# AMR3350.net
KiCad netlist of a schematic drawn in EAGLE
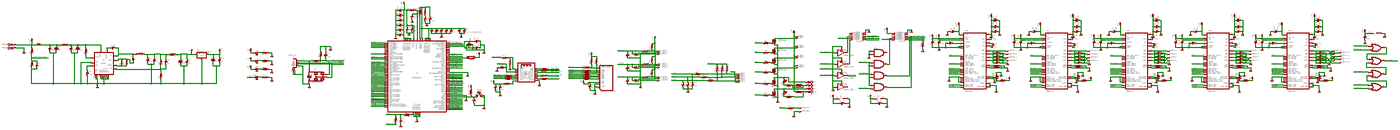
[diagram p0: schematic, sheet 1, overview]
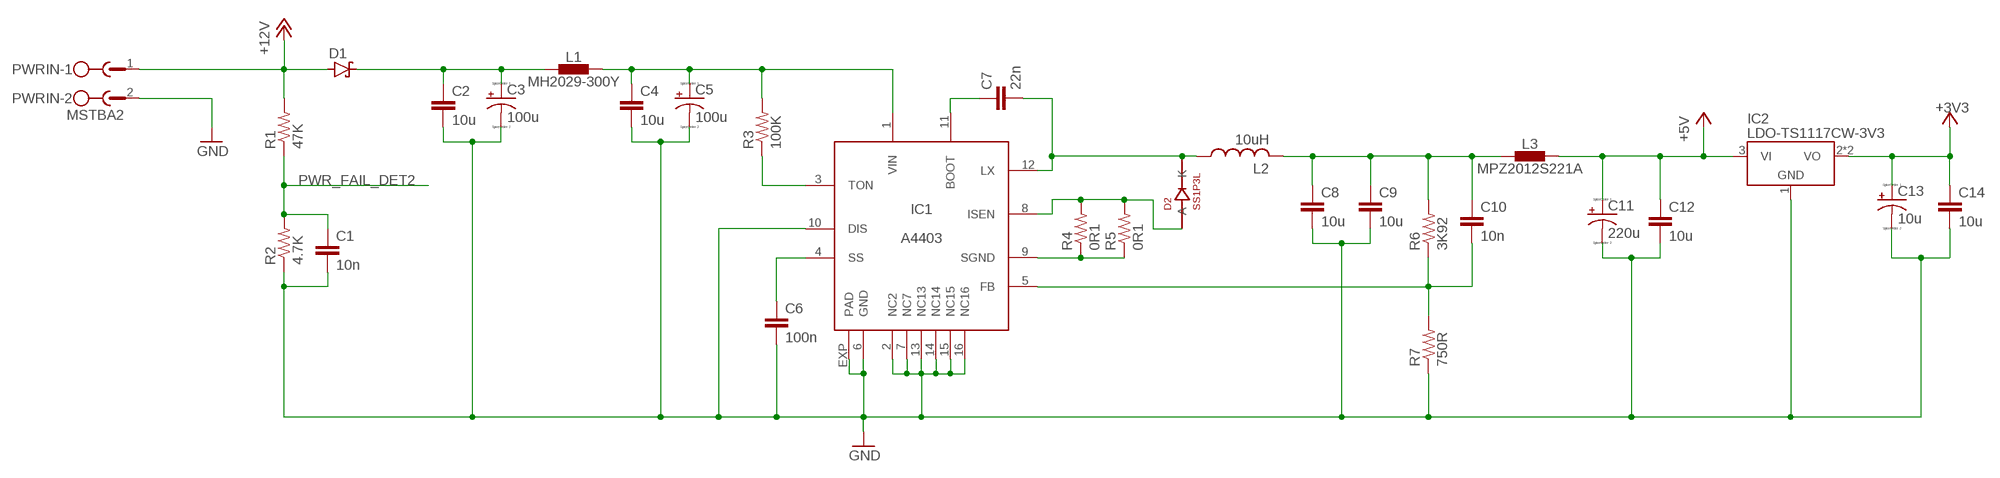
[diagram p1: schematic, sheet 1, part 1 of 6]
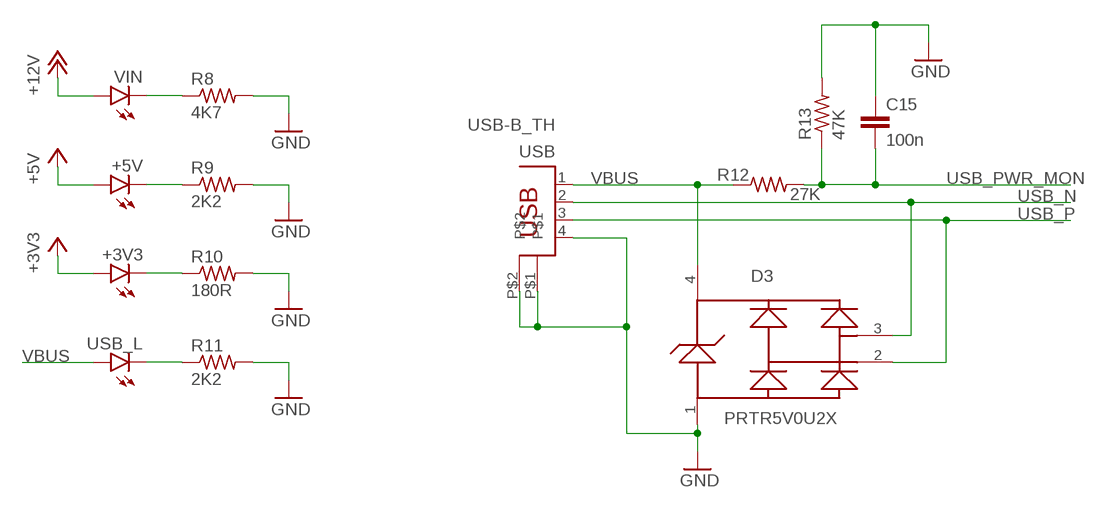
[diagram p2: schematic, sheet 1, part 2 of 6]
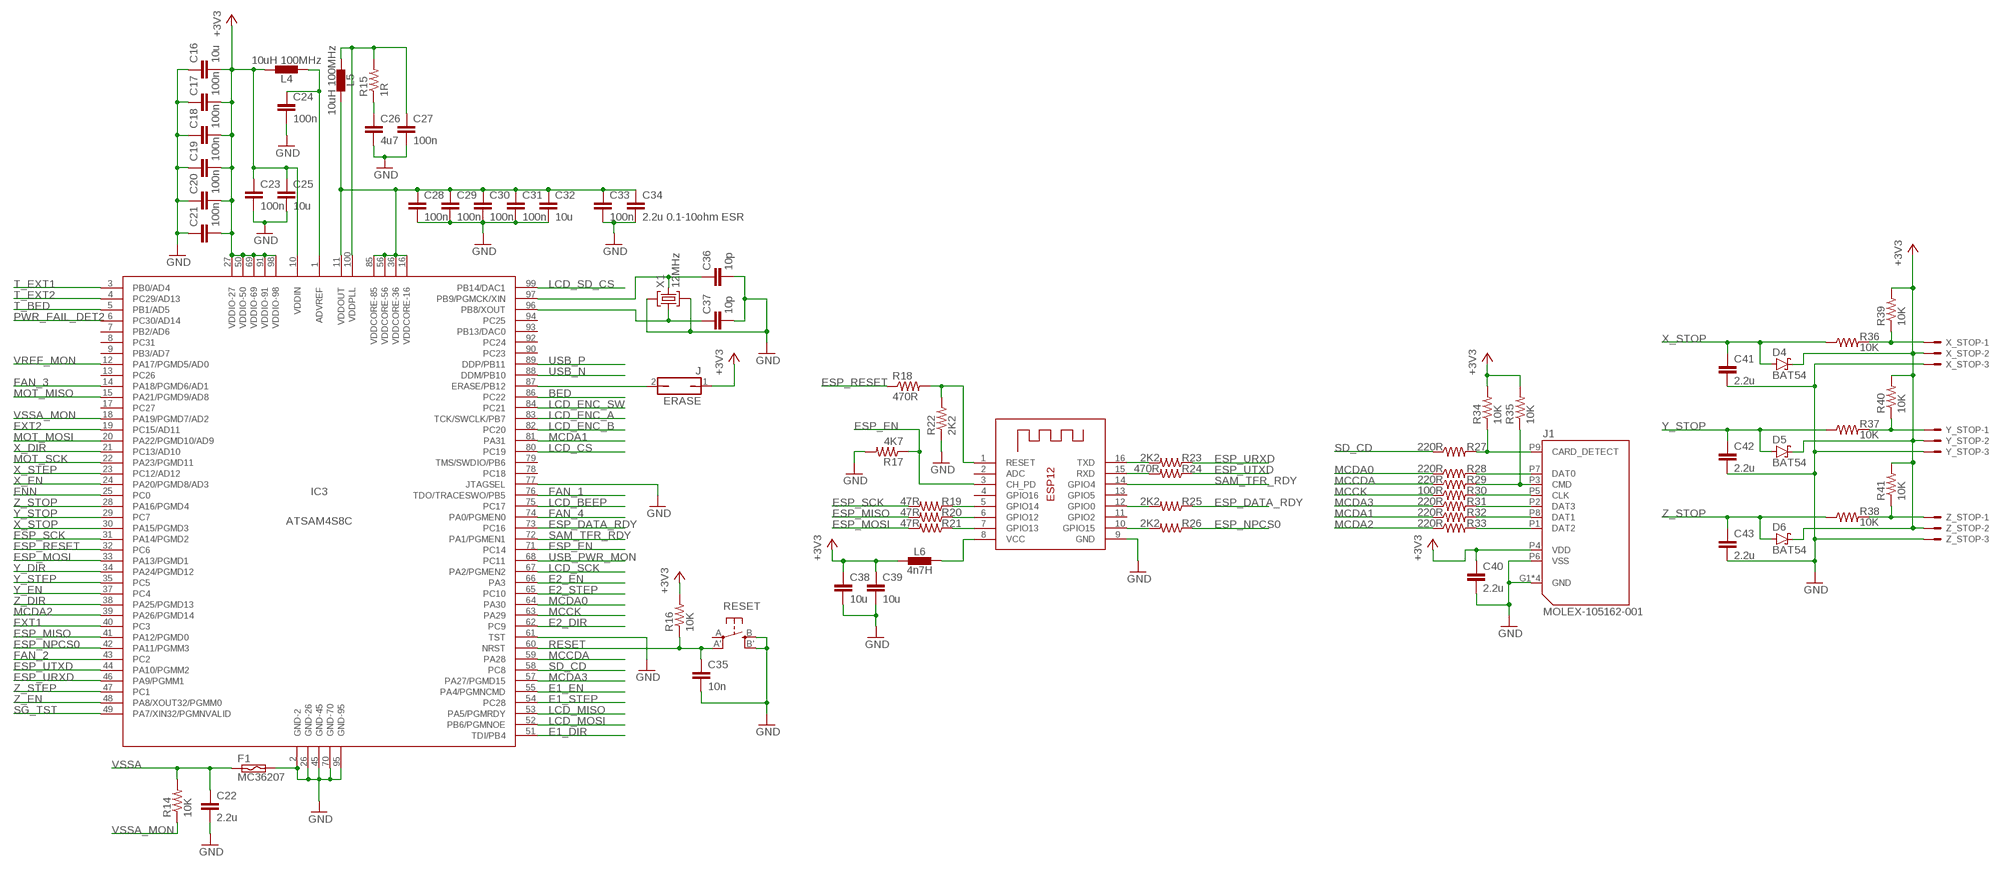
[diagram p3: schematic, sheet 1, part 3 of 6]
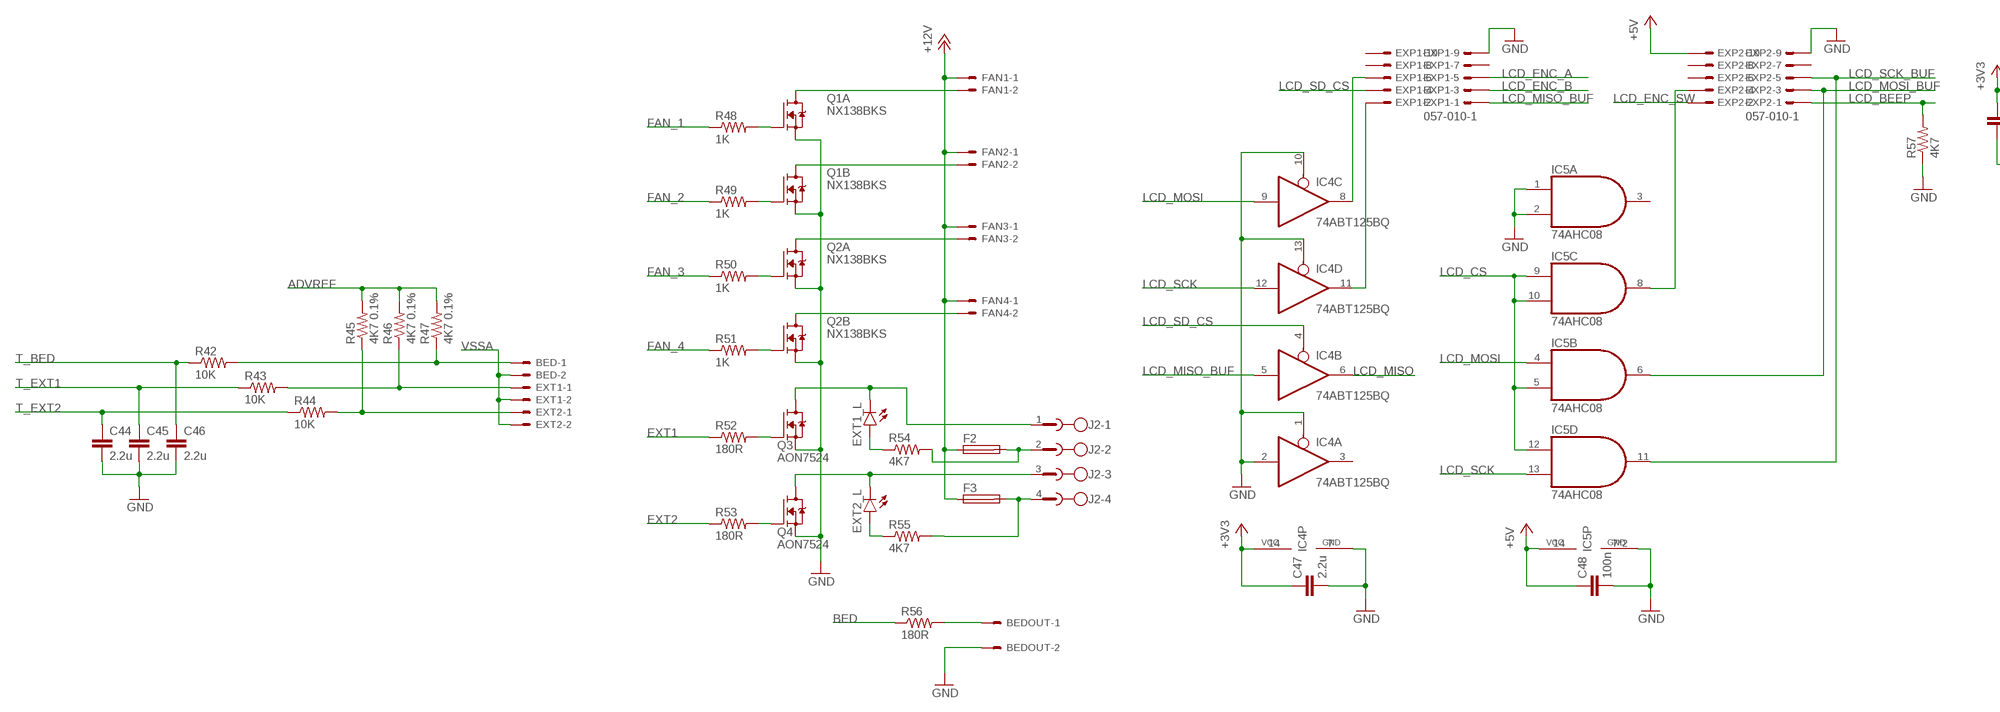
[diagram p4: schematic, sheet 1, part 4 of 6]
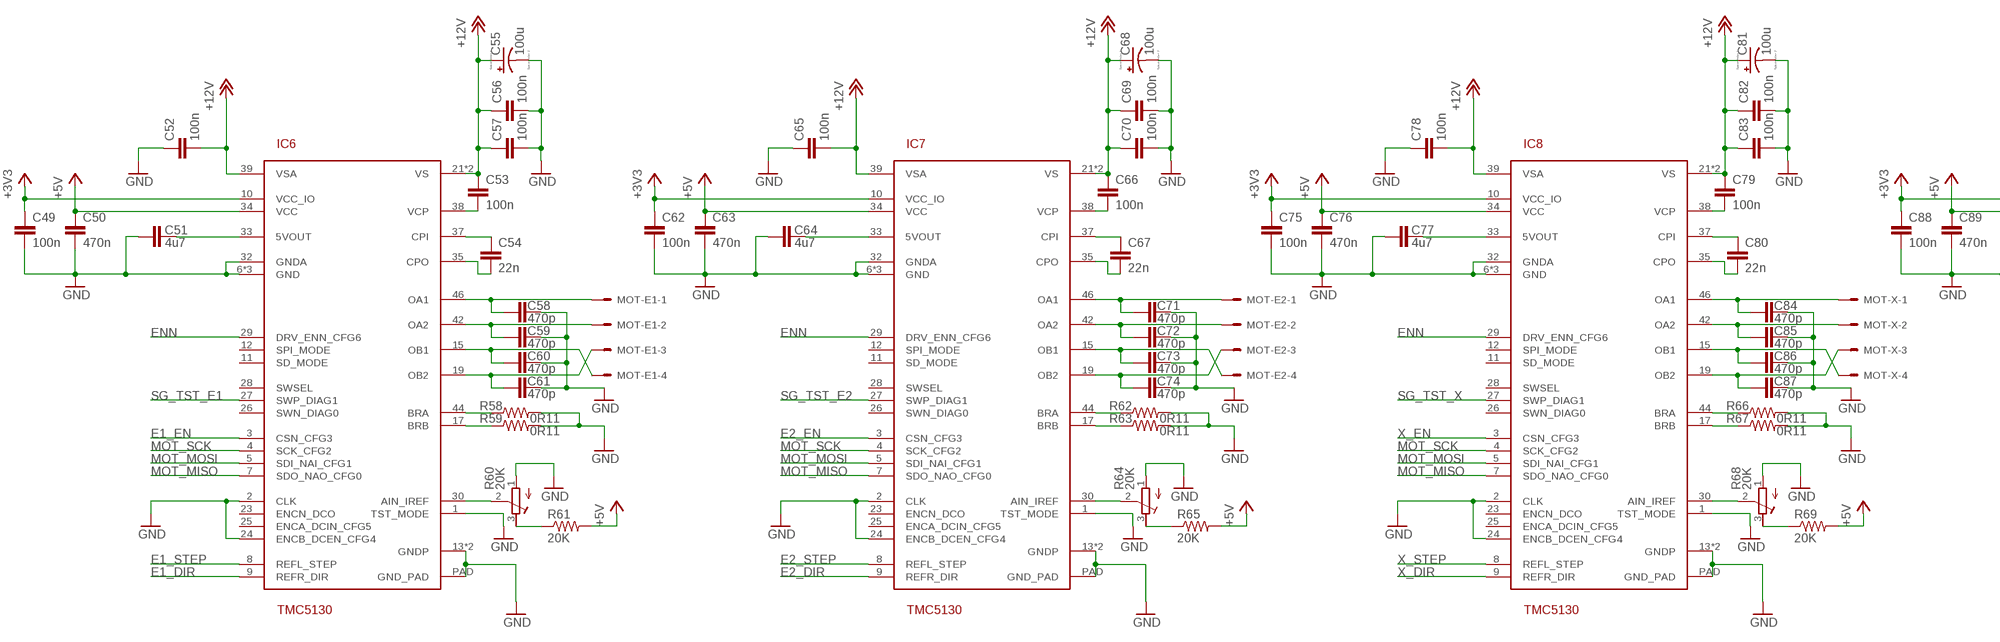
[diagram p5: schematic, sheet 1, part 5 of 6]
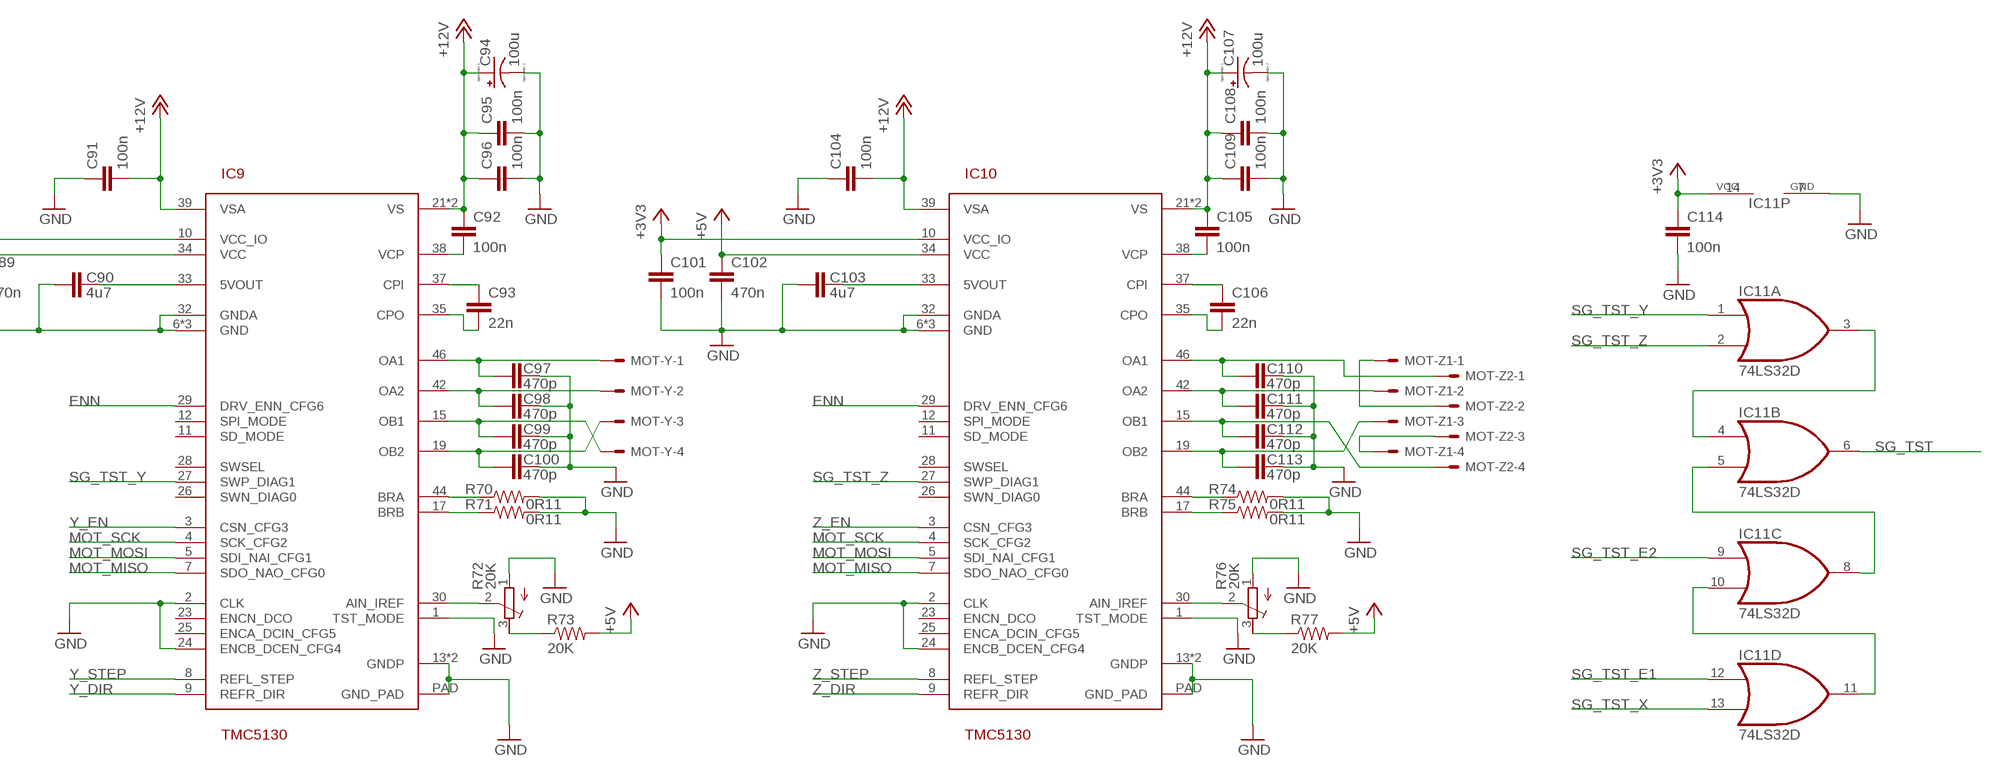
[diagram p6: schematic, sheet 1, part 6 of 6]

(export (version "E")
  (design (tool "Eeschema 10.0.6"))
  (components
    (comp (ref "+3V3")
      (value "LEDCHIPLED_0805")
      (footprint "eagle-import:CHIPLED_0805")
      (libsource (lib "eagle-import") (part "LEDCHIPLED_0805"))
    )
    (comp (ref "+5V")
      (value "LEDCHIPLED_0805")
      (footprint "eagle-import:CHIPLED_0805")
      (libsource (lib "eagle-import") (part "LEDCHIPLED_0805"))
    )
    (comp (ref "BED")
      (value "KK-254-2")
      (footprint "eagle-import:MOLEX-KK-254-2")
      (libsource (lib "eagle-import") (part "KK-254-2"))
    )
    (comp (ref "BEDOUT")
      (value "KK-254-2")
      (footprint "eagle-import:MOLEX-KK-254-2")
      (libsource (lib "eagle-import") (part "KK-254-2"))
    )
    (comp (ref "C1")
      (value "10n")
      (footprint "eagle-import:C0603")
      (libsource (lib "eagle-import") (part "resistor_348_C-EUC0603"))
    )
    (comp (ref "C2")
      (value "10u")
      (footprint "eagle-import:C0603")
      (libsource (lib "eagle-import") (part "resistor_348_C-EUC0603"))
    )
    (comp (ref "C3")
      (value "100u")
      (footprint "eagle-import:PANASONIC_D")
      (libsource (lib "eagle-import") (part "CPOL-USD"))
    )
    (comp (ref "C4")
      (value "10u")
      (footprint "eagle-import:C0603")
      (libsource (lib "eagle-import") (part "resistor_348_C-EUC0603"))
    )
    (comp (ref "C5")
      (value "100u")
      (footprint "eagle-import:PANASONIC_D")
      (libsource (lib "eagle-import") (part "CPOL-USD"))
    )
    (comp (ref "C6")
      (value "100n")
      (footprint "eagle-import:C0603")
      (libsource (lib "eagle-import") (part "resistor_348_C-EUC0603"))
    )
    (comp (ref "C7")
      (value "22n")
      (footprint "eagle-import:C0603")
      (libsource (lib "eagle-import") (part "resistor_348_C-EUC0603"))
    )
    (comp (ref "C8")
      (value "10u")
      (footprint "eagle-import:C0603")
      (libsource (lib "eagle-import") (part "resistor_348_C-EUC0603"))
    )
    (comp (ref "C9")
      (value "10u")
      (footprint "eagle-import:C0603")
      (libsource (lib "eagle-import") (part "resistor_348_C-EUC0603"))
    )
    (comp (ref "C10")
      (value "10n")
      (footprint "eagle-import:C0603")
      (libsource (lib "eagle-import") (part "resistor_348_C-EUC0603"))
    )
    (comp (ref "C11")
      (value "220u")
      (footprint "eagle-import:PANASONIC_D")
      (libsource (lib "eagle-import") (part "CPOL-USD"))
    )
    (comp (ref "C12")
      (value "10u")
      (footprint "eagle-import:C0603")
      (libsource (lib "eagle-import") (part "resistor_348_C-EUC0603"))
    )
    (comp (ref "C13")
      (value "10u")
      (footprint "eagle-import:PANASONIC_D")
      (libsource (lib "eagle-import") (part "CPOL-USD"))
    )
    (comp (ref "C14")
      (value "10u")
      (footprint "eagle-import:C0603")
      (libsource (lib "eagle-import") (part "resistor_348_C-EUC0603"))
    )
    (comp (ref "C15")
      (value "100n")
      (footprint "eagle-import:C0603")
      (libsource (lib "eagle-import") (part "resistor_348_C-EUC0603"))
    )
    (comp (ref "C16")
      (value "10u")
      (footprint "eagle-import:C0805")
      (libsource (lib "eagle-import") (part "resistor_348_C-EUC0805"))
    )
    (comp (ref "C17")
      (value "100n")
      (footprint "eagle-import:C0603")
      (libsource (lib "eagle-import") (part "resistor_348_C-EUC0603"))
    )
    (comp (ref "C18")
      (value "100n")
      (footprint "eagle-import:C0603")
      (libsource (lib "eagle-import") (part "resistor_348_C-EUC0603"))
    )
    (comp (ref "C19")
      (value "100n")
      (footprint "eagle-import:C0603")
      (libsource (lib "eagle-import") (part "resistor_348_C-EUC0603"))
    )
    (comp (ref "C20")
      (value "100n")
      (footprint "eagle-import:C0603")
      (libsource (lib "eagle-import") (part "resistor_348_C-EUC0603"))
    )
    (comp (ref "C21")
      (value "100n")
      (footprint "eagle-import:C0603")
      (libsource (lib "eagle-import") (part "resistor_348_C-EUC0603"))
    )
    (comp (ref "C22")
      (value "2.2u")
      (footprint "eagle-import:C0603")
      (libsource (lib "eagle-import") (part "resistor_348_C-EUC0603"))
    )
    (comp (ref "C23")
      (value "100n")
      (footprint "eagle-import:C0603")
      (libsource (lib "eagle-import") (part "resistor_348_C-EUC0603"))
    )
    (comp (ref "C24")
      (value "100n")
      (footprint "eagle-import:C0603")
      (libsource (lib "eagle-import") (part "resistor_348_C-EUC0603"))
    )
    (comp (ref "C25")
      (value "10u")
      (footprint "eagle-import:C0603")
      (libsource (lib "eagle-import") (part "resistor_348_C-EUC0603"))
    )
    (comp (ref "C26")
      (value "4u7")
      (footprint "eagle-import:C0603")
      (libsource (lib "eagle-import") (part "resistor_348_C-EUC0603"))
    )
    (comp (ref "C27")
      (value "100n")
      (footprint "eagle-import:C0603")
      (libsource (lib "eagle-import") (part "resistor_348_C-EUC0603"))
    )
    (comp (ref "C28")
      (value "100n")
      (footprint "eagle-import:C0603")
      (libsource (lib "eagle-import") (part "resistor_348_C-EUC0603"))
    )
    (comp (ref "C29")
      (value "100n")
      (footprint "eagle-import:C0603")
      (libsource (lib "eagle-import") (part "resistor_348_C-EUC0603"))
    )
    (comp (ref "C30")
      (value "100n")
      (footprint "eagle-import:C0603")
      (libsource (lib "eagle-import") (part "resistor_348_C-EUC0603"))
    )
    (comp (ref "C31")
      (value "100n")
      (footprint "eagle-import:C0603")
      (libsource (lib "eagle-import") (part "resistor_348_C-EUC0603"))
    )
    (comp (ref "C32")
      (value "10u")
      (footprint "eagle-import:C0805")
      (libsource (lib "eagle-import") (part "resistor_348_C-EUC0805"))
    )
    (comp (ref "C33")
      (value "100n")
      (footprint "eagle-import:C0603")
      (libsource (lib "eagle-import") (part "resistor_348_C-EUC0603"))
    )
    (comp (ref "C34")
      (value "2.2u 0.1-10ohm ESR")
      (footprint "eagle-import:C0603")
      (libsource (lib "eagle-import") (part "resistor_348_C-EUC0603"))
    )
    (comp (ref "C35")
      (value "10n")
      (footprint "eagle-import:C0603")
      (libsource (lib "eagle-import") (part "resistor_348_C-EUC0603"))
    )
    (comp (ref "C36")
      (value "10p")
      (footprint "eagle-import:C0603")
      (libsource (lib "eagle-import") (part "resistor_348_C-EUC0603"))
    )
    (comp (ref "C37")
      (value "10p")
      (footprint "eagle-import:C0603")
      (libsource (lib "eagle-import") (part "resistor_348_C-EUC0603"))
    )
    (comp (ref "C38")
      (value "10u")
      (footprint "eagle-import:C0603")
      (libsource (lib "eagle-import") (part "resistor_348_C-EUC0603"))
    )
    (comp (ref "C39")
      (value "10u")
      (footprint "eagle-import:C0603")
      (libsource (lib "eagle-import") (part "resistor_348_C-EUC0603"))
    )
    (comp (ref "C40")
      (value "2.2u")
      (footprint "eagle-import:C0603")
      (libsource (lib "eagle-import") (part "resistor_348_C-EUC0603"))
    )
    (comp (ref "C41")
      (value "2.2u")
      (footprint "eagle-import:C0603")
      (libsource (lib "eagle-import") (part "resistor_348_C-EUC0603"))
    )
    (comp (ref "C42")
      (value "2.2u")
      (footprint "eagle-import:C0603")
      (libsource (lib "eagle-import") (part "resistor_348_C-EUC0603"))
    )
    (comp (ref "C43")
      (value "2.2u")
      (footprint "eagle-import:C0603")
      (libsource (lib "eagle-import") (part "resistor_348_C-EUC0603"))
    )
    (comp (ref "C44")
      (value "2.2u")
      (footprint "eagle-import:C0603")
      (libsource (lib "eagle-import") (part "resistor_348_C-EUC0603"))
    )
    (comp (ref "C45")
      (value "2.2u")
      (footprint "eagle-import:C0603")
      (libsource (lib "eagle-import") (part "resistor_348_C-EUC0603"))
    )
    (comp (ref "C46")
      (value "2.2u")
      (footprint "eagle-import:C0603")
      (libsource (lib "eagle-import") (part "resistor_348_C-EUC0603"))
    )
    (comp (ref "C47")
      (value "2.2u")
      (footprint "eagle-import:C0603")
      (libsource (lib "eagle-import") (part "resistor_348_C-EUC0603"))
    )
    (comp (ref "C48")
      (value "100n")
      (footprint "eagle-import:C0603")
      (libsource (lib "eagle-import") (part "resistor_348_C-EUC0603"))
    )
    (comp (ref "C49")
      (value "100n")
      (footprint "eagle-import:C0603")
      (libsource (lib "eagle-import") (part "resistor_348_C-EUC0603"))
    )
    (comp (ref "C50")
      (value "470n")
      (footprint "eagle-import:C0603")
      (libsource (lib "eagle-import") (part "resistor_348_C-EUC0603"))
    )
    (comp (ref "C51")
      (value "4u7")
      (footprint "eagle-import:C0603")
      (libsource (lib "eagle-import") (part "resistor_348_C-EUC0603"))
    )
    (comp (ref "C52")
      (value "100n")
      (footprint "eagle-import:C0603")
      (libsource (lib "eagle-import") (part "resistor_348_C-EUC0603"))
    )
    (comp (ref "C53")
      (value "100n")
      (footprint "eagle-import:C0603")
      (libsource (lib "eagle-import") (part "resistor_348_C-EUC0603"))
    )
    (comp (ref "C54")
      (value "22n")
      (footprint "eagle-import:C0603")
      (libsource (lib "eagle-import") (part "resistor_348_C-EUC0603"))
    )
    (comp (ref "C55")
      (value "100u")
      (footprint "eagle-import:PANASONIC_D")
      (libsource (lib "eagle-import") (part "CPOL-USD"))
    )
    (comp (ref "C56")
      (value "100n")
      (footprint "eagle-import:C0603")
      (libsource (lib "eagle-import") (part "resistor_348_C-EUC0603"))
    )
    (comp (ref "C57")
      (value "100n")
      (footprint "eagle-import:C0603")
      (libsource (lib "eagle-import") (part "resistor_348_C-EUC0603"))
    )
    (comp (ref "C58")
      (value "470p")
      (footprint "eagle-import:C0402")
      (libsource (lib "eagle-import") (part "resistor_348_C-EUC0402"))
    )
    (comp (ref "C59")
      (value "470p")
      (footprint "eagle-import:C0402")
      (libsource (lib "eagle-import") (part "resistor_348_C-EUC0402"))
    )
    (comp (ref "C60")
      (value "470p")
      (footprint "eagle-import:C0402")
      (libsource (lib "eagle-import") (part "resistor_348_C-EUC0402"))
    )
    (comp (ref "C61")
      (value "470p")
      (footprint "eagle-import:C0402")
      (libsource (lib "eagle-import") (part "resistor_348_C-EUC0402"))
    )
    (comp (ref "C62")
      (value "100n")
      (footprint "eagle-import:C0603")
      (libsource (lib "eagle-import") (part "resistor_348_C-EUC0603"))
    )
    (comp (ref "C63")
      (value "470n")
      (footprint "eagle-import:C0603")
      (libsource (lib "eagle-import") (part "resistor_348_C-EUC0603"))
    )
    (comp (ref "C64")
      (value "4u7")
      (footprint "eagle-import:C0603")
      (libsource (lib "eagle-import") (part "resistor_348_C-EUC0603"))
    )
    (comp (ref "C65")
      (value "100n")
      (footprint "eagle-import:C0603")
      (libsource (lib "eagle-import") (part "resistor_348_C-EUC0603"))
    )
    (comp (ref "C66")
      (value "100n")
      (footprint "eagle-import:C0603")
      (libsource (lib "eagle-import") (part "resistor_348_C-EUC0603"))
    )
    (comp (ref "C67")
      (value "22n")
      (footprint "eagle-import:C0603")
      (libsource (lib "eagle-import") (part "resistor_348_C-EUC0603"))
    )
    (comp (ref "C68")
      (value "100u")
      (footprint "eagle-import:PANASONIC_D")
      (libsource (lib "eagle-import") (part "CPOL-USD"))
    )
    (comp (ref "C69")
      (value "100n")
      (footprint "eagle-import:C0603")
      (libsource (lib "eagle-import") (part "resistor_348_C-EUC0603"))
    )
    (comp (ref "C70")
      (value "100n")
      (footprint "eagle-import:C0603")
      (libsource (lib "eagle-import") (part "resistor_348_C-EUC0603"))
    )
    (comp (ref "C71")
      (value "470p")
      (footprint "eagle-import:C0402")
      (libsource (lib "eagle-import") (part "resistor_348_C-EUC0402"))
    )
    (comp (ref "C72")
      (value "470p")
      (footprint "eagle-import:C0402")
      (libsource (lib "eagle-import") (part "resistor_348_C-EUC0402"))
    )
    (comp (ref "C73")
      (value "470p")
      (footprint "eagle-import:C0402")
      (libsource (lib "eagle-import") (part "resistor_348_C-EUC0402"))
    )
    (comp (ref "C74")
      (value "470p")
      (footprint "eagle-import:C0402")
      (libsource (lib "eagle-import") (part "resistor_348_C-EUC0402"))
    )
    (comp (ref "C75")
      (value "100n")
      (footprint "eagle-import:C0603")
      (libsource (lib "eagle-import") (part "resistor_348_C-EUC0603"))
    )
    (comp (ref "C76")
      (value "470n")
      (footprint "eagle-import:C0603")
      (libsource (lib "eagle-import") (part "resistor_348_C-EUC0603"))
    )
    (comp (ref "C77")
      (value "4u7")
      (footprint "eagle-import:C0603")
      (libsource (lib "eagle-import") (part "resistor_348_C-EUC0603"))
    )
    (comp (ref "C78")
      (value "100n")
      (footprint "eagle-import:C0603")
      (libsource (lib "eagle-import") (part "resistor_348_C-EUC0603"))
    )
    (comp (ref "C79")
      (value "100n")
      (footprint "eagle-import:C0603")
      (libsource (lib "eagle-import") (part "resistor_348_C-EUC0603"))
    )
    (comp (ref "C80")
      (value "22n")
      (footprint "eagle-import:C0603")
      (libsource (lib "eagle-import") (part "resistor_348_C-EUC0603"))
    )
    (comp (ref "C81")
      (value "100u")
      (footprint "eagle-import:PANASONIC_D")
      (libsource (lib "eagle-import") (part "CPOL-USD"))
    )
    (comp (ref "C82")
      (value "100n")
      (footprint "eagle-import:C0603")
      (libsource (lib "eagle-import") (part "resistor_348_C-EUC0603"))
    )
    (comp (ref "C83")
      (value "100n")
      (footprint "eagle-import:C0603")
      (libsource (lib "eagle-import") (part "resistor_348_C-EUC0603"))
    )
    (comp (ref "C84")
      (value "470p")
      (footprint "eagle-import:C0402")
      (libsource (lib "eagle-import") (part "resistor_348_C-EUC0402"))
    )
    (comp (ref "C85")
      (value "470p")
      (footprint "eagle-import:C0402")
      (libsource (lib "eagle-import") (part "resistor_348_C-EUC0402"))
    )
    (comp (ref "C86")
      (value "470p")
      (footprint "eagle-import:C0402")
      (libsource (lib "eagle-import") (part "resistor_348_C-EUC0402"))
    )
    (comp (ref "C87")
      (value "470p")
      (footprint "eagle-import:C0402")
      (libsource (lib "eagle-import") (part "resistor_348_C-EUC0402"))
    )
    (comp (ref "C88")
      (value "100n")
      (footprint "eagle-import:C0603")
      (libsource (lib "eagle-import") (part "resistor_348_C-EUC0603"))
    )
    (comp (ref "C89")
      (value "470n")
      (footprint "eagle-import:C0603")
      (libsource (lib "eagle-import") (part "resistor_348_C-EUC0603"))
    )
    (comp (ref "C90")
      (value "4u7")
      (footprint "eagle-import:C0603")
      (libsource (lib "eagle-import") (part "resistor_348_C-EUC0603"))
    )
    (comp (ref "C91")
      (value "100n")
      (footprint "eagle-import:C0603")
      (libsource (lib "eagle-import") (part "resistor_348_C-EUC0603"))
    )
    (comp (ref "C92")
      (value "100n")
      (footprint "eagle-import:C0603")
      (libsource (lib "eagle-import") (part "resistor_348_C-EUC0603"))
    )
    (comp (ref "C93")
      (value "22n")
      (footprint "eagle-import:C0603")
      (libsource (lib "eagle-import") (part "resistor_348_C-EUC0603"))
    )
    (comp (ref "C94")
      (value "100u")
      (footprint "eagle-import:PANASONIC_D")
      (libsource (lib "eagle-import") (part "CPOL-USD"))
    )
    (comp (ref "C95")
      (value "100n")
      (footprint "eagle-import:C0603")
      (libsource (lib "eagle-import") (part "resistor_348_C-EUC0603"))
    )
    (comp (ref "C96")
      (value "100n")
      (footprint "eagle-import:C0603")
      (libsource (lib "eagle-import") (part "resistor_348_C-EUC0603"))
    )
    (comp (ref "C97")
      (value "470p")
      (footprint "eagle-import:C0402")
      (libsource (lib "eagle-import") (part "resistor_348_C-EUC0402"))
    )
    (comp (ref "C98")
      (value "470p")
      (footprint "eagle-import:C0402")
      (libsource (lib "eagle-import") (part "resistor_348_C-EUC0402"))
    )
    (comp (ref "C99")
      (value "470p")
      (footprint "eagle-import:C0402")
      (libsource (lib "eagle-import") (part "resistor_348_C-EUC0402"))
    )
    (comp (ref "C100")
      (value "470p")
      (footprint "eagle-import:C0402")
      (libsource (lib "eagle-import") (part "resistor_348_C-EUC0402"))
    )
    (comp (ref "C101")
      (value "100n")
      (footprint "eagle-import:C0603")
      (libsource (lib "eagle-import") (part "resistor_348_C-EUC0603"))
    )
    (comp (ref "C102")
      (value "470n")
      (footprint "eagle-import:C0603")
      (libsource (lib "eagle-import") (part "resistor_348_C-EUC0603"))
    )
    (comp (ref "C103")
      (value "4u7")
      (footprint "eagle-import:C0603")
      (libsource (lib "eagle-import") (part "resistor_348_C-EUC0603"))
    )
    (comp (ref "C104")
      (value "100n")
      (footprint "eagle-import:C0603")
      (libsource (lib "eagle-import") (part "resistor_348_C-EUC0603"))
    )
    (comp (ref "C105")
      (value "100n")
      (footprint "eagle-import:C0603")
      (libsource (lib "eagle-import") (part "resistor_348_C-EUC0603"))
    )
    (comp (ref "C106")
      (value "22n")
      (footprint "eagle-import:C0603")
      (libsource (lib "eagle-import") (part "resistor_348_C-EUC0603"))
    )
    (comp (ref "C107")
      (value "100u")
      (footprint "eagle-import:PANASONIC_D")
      (libsource (lib "eagle-import") (part "CPOL-USD"))
    )
    (comp (ref "C108")
      (value "100n")
      (footprint "eagle-import:C0603")
      (libsource (lib "eagle-import") (part "resistor_348_C-EUC0603"))
    )
    (comp (ref "C109")
      (value "100n")
      (footprint "eagle-import:C0603")
      (libsource (lib "eagle-import") (part "resistor_348_C-EUC0603"))
    )
    (comp (ref "C110")
      (value "470p")
      (footprint "eagle-import:C0402")
      (libsource (lib "eagle-import") (part "resistor_348_C-EUC0402"))
    )
    (comp (ref "C111")
      (value "470p")
      (footprint "eagle-import:C0402")
      (libsource (lib "eagle-import") (part "resistor_348_C-EUC0402"))
    )
    (comp (ref "C112")
      (value "470p")
      (footprint "eagle-import:C0402")
      (libsource (lib "eagle-import") (part "resistor_348_C-EUC0402"))
    )
    (comp (ref "C113")
      (value "470p")
      (footprint "eagle-import:C0402")
      (libsource (lib "eagle-import") (part "resistor_348_C-EUC0402"))
    )
    (comp (ref "C114")
      (value "100n")
      (footprint "eagle-import:C0603")
      (libsource (lib "eagle-import") (part "C-EUC0603"))
    )
    (comp (ref "D1")
      (value "SCHOTTKY-DIODESMD")
      (footprint "eagle-import:SMB")
      (libsource (lib "eagle-import") (part "SCHOTTKY-DIODESMD"))
    )
    (comp (ref "D2")
      (value "SS1P3L")
      (footprint "eagle-import:DO220AAL")
      (fields (field (name "PART_NUMBER") "SS1P3L-M3/84A"))
      (libsource (lib "eagle-import") (part "0025_SS1P3L-M3/84A"))
    )
    (comp (ref "D3")
      (value "PRTR5V0U2XB")
      (footprint "eagle-import:SOT143B")
      (libsource (lib "eagle-import") (part "PRTR5V0U2XB"))
    )
    (comp (ref "D4")
      (value "BAT54")
      (footprint "eagle-import:SOT23")
      (libsource (lib "eagle-import") (part "BAT54"))
    )
    (comp (ref "D5")
      (value "BAT54")
      (footprint "eagle-import:SOT23")
      (libsource (lib "eagle-import") (part "BAT54"))
    )
    (comp (ref "D6")
      (value "BAT54")
      (footprint "eagle-import:SOT23")
      (libsource (lib "eagle-import") (part "BAT54"))
    )
    (comp (ref "ERASE")
      (value "J")
      (footprint "eagle-import:1X02")
      (libsource (lib "eagle-import") (part "J"))
    )
    (comp (ref "ESP8266")
      (value "ESP-12")
      (footprint "eagle-import:ESP-12")
      (libsource (lib "eagle-import") (part "ESP-12"))
    )
    (comp (ref "EXP1")
      (value "057-010-1")
      (footprint "eagle-import:057-010-1")
      (libsource (lib "eagle-import") (part "057-010-1"))
    )
    (comp (ref "EXP2")
      (value "057-010-1")
      (footprint "eagle-import:057-010-1")
      (libsource (lib "eagle-import") (part "057-010-1"))
    )
    (comp (ref "EXT1")
      (value "KK-254-2")
      (footprint "eagle-import:MOLEX-KK-254-2")
      (libsource (lib "eagle-import") (part "KK-254-2"))
    )
    (comp (ref "EXT1_L")
      (value "LEDCHIPLED_0805")
      (footprint "eagle-import:CHIPLED_0805")
      (libsource (lib "eagle-import") (part "LEDCHIPLED_0805"))
    )
    (comp (ref "EXT2")
      (value "KK-254-2")
      (footprint "eagle-import:MOLEX-KK-254-2")
      (libsource (lib "eagle-import") (part "KK-254-2"))
    )
    (comp (ref "EXT2_L")
      (value "LEDCHIPLED_0805")
      (footprint "eagle-import:CHIPLED_0805")
      (libsource (lib "eagle-import") (part "LEDCHIPLED_0805"))
    )
    (comp (ref "F1")
      (value "MC36207")
      (footprint "eagle-import:MC36207")
      (libsource (lib "eagle-import") (part "MC36207"))
    )
    (comp (ref "F2")
      (value "19560")
      (footprint "eagle-import:19560")
      (fields (field (name "MPN") "56000001009"))
      (libsource (lib "eagle-import") (part "19560"))
    )
    (comp (ref "F3")
      (value "19560")
      (footprint "eagle-import:19560")
      (fields (field (name "MPN") "56000001009"))
      (libsource (lib "eagle-import") (part "19560"))
    )
    (comp (ref "FAN1")
      (value "KK-254-2")
      (footprint "eagle-import:MOLEX-KK-254-2")
      (libsource (lib "eagle-import") (part "KK-254-2"))
    )
    (comp (ref "FAN2")
      (value "KK-254-2")
      (footprint "eagle-import:MOLEX-KK-254-2")
      (libsource (lib "eagle-import") (part "KK-254-2"))
    )
    (comp (ref "FAN3")
      (value "KK-254-2")
      (footprint "eagle-import:MOLEX-KK-254-2")
      (libsource (lib "eagle-import") (part "KK-254-2"))
    )
    (comp (ref "FAN4")
      (value "KK-254-2")
      (footprint "eagle-import:MOLEX-KK-254-2")
      (libsource (lib "eagle-import") (part "KK-254-2"))
    )
    (comp (ref "IC1")
      (value "A4403")
      (footprint "eagle-import:QFN16-4X4")
      (libsource (lib "eagle-import") (part "A4403"))
    )
    (comp (ref "IC2")
      (value "LDO-TS1117CW-3V3")
      (footprint "eagle-import:SOT223")
      (libsource (lib "eagle-import") (part "LDO-TS1117CW-3V3"))
    )
    (comp (ref "IC3")
      (value "ATSAM4S8C")
      (footprint "eagle-import:LQFP100")
      (libsource (lib "eagle-import") (part "ATSAM4S8C"))
    )
    (comp (ref "IC4")
      (value "74ABT125BQ")
      (footprint "eagle-import:DHVQFN14")
      (libsource (lib "eagle-import") (part "74125BQABT"))
    )
    (comp (ref "IC5")
      (value "74AHC08")
      (footprint "eagle-import:DHVQFN14")
      (libsource (lib "eagle-import") (part "74AHC08"))
    )
    (comp (ref "IC6")
      (value "TMC5130")
      (footprint "eagle-import:QFP50P900X900X113-49N_NOFID")
      (libsource (lib "eagle-import") (part "TMC5130"))
    )
    (comp (ref "IC7")
      (value "TMC5130")
      (footprint "eagle-import:QFP50P900X900X113-49N_NOFID")
      (libsource (lib "eagle-import") (part "TMC5130"))
    )
    (comp (ref "IC8")
      (value "TMC5130")
      (footprint "eagle-import:QFP50P900X900X113-49N_NOFID")
      (libsource (lib "eagle-import") (part "TMC5130"))
    )
    (comp (ref "IC9")
      (value "TMC5130")
      (footprint "eagle-import:QFP50P900X900X113-49N_NOFID")
      (libsource (lib "eagle-import") (part "TMC5130"))
    )
    (comp (ref "IC10")
      (value "TMC5130")
      (footprint "eagle-import:QFP50P900X900X113-49N_NOFID")
      (libsource (lib "eagle-import") (part "TMC5130"))
    )
    (comp (ref "IC11")
      (value "74LS32D")
      (footprint "eagle-import:SO14")
      (libsource (lib "eagle-import") (part "7432DLS"))
    )
    (comp (ref "J1")
      (value "MOLEX-105162-001")
      (footprint "eagle-import:MOLEX-105162")
      (libsource (lib "eagle-import") (part "MOLEX-105162-001"))
    )
    (comp (ref "J2")
      (value "MSTBV4")
      (footprint "eagle-import:MSTBV4")
      (fields (field (name "MPN") "MSTBV 2,5/4-GF-5.08"))
      (libsource (lib "eagle-import") (part "MSTBV4"))
    )
    (comp (ref "L1")
      (value "MH2029-300Y")
      (footprint "eagle-import:C0805")
      (libsource (lib "eagle-import") (part "INDUCTOR-0805"))
    )
    (comp (ref "L2")
      (value "10uH")
      (footprint "eagle-import:SRR0604")
      (libsource (lib "eagle-import") (part "L-USSRR0604"))
    )
    (comp (ref "L3")
      (value "MPZ2012S221A")
      (footprint "eagle-import:C0805")
      (libsource (lib "eagle-import") (part "INDUCTOR-0805"))
    )
    (comp (ref "L4")
      (value "10uH 100MHz")
      (footprint "eagle-import:C0603")
      (libsource (lib "eagle-import") (part "Zero_V1.0_INDUCTOR-0603"))
    )
    (comp (ref "L5")
      (value "10uH 100MHz")
      (footprint "eagle-import:C0603")
      (libsource (lib "eagle-import") (part "Zero_V1.0_INDUCTOR-0603"))
    )
    (comp (ref "L6")
      (value "4n7H")
      (footprint "eagle-import:C0603")
      (libsource (lib "eagle-import") (part "Zero_V1.0_INDUCTOR-0603"))
    )
    (comp (ref "MOT-E1")
      (value "KK-254-4")
      (footprint "eagle-import:MOLEX-KK-254-4")
      (libsource (lib "eagle-import") (part "KK-254-4"))
    )
    (comp (ref "MOT-E2")
      (value "KK-254-4")
      (footprint "eagle-import:MOLEX-KK-254-4")
      (libsource (lib "eagle-import") (part "KK-254-4"))
    )
    (comp (ref "MOT-X")
      (value "KK-254-4")
      (footprint "eagle-import:MOLEX-KK-254-4")
      (libsource (lib "eagle-import") (part "KK-254-4"))
    )
    (comp (ref "MOT-Y")
      (value "KK-254-4")
      (footprint "eagle-import:MOLEX-KK-254-4")
      (libsource (lib "eagle-import") (part "KK-254-4"))
    )
    (comp (ref "MOT-Z1")
      (value "KK-254-4")
      (footprint "eagle-import:MOLEX-KK-254-4")
      (libsource (lib "eagle-import") (part "KK-254-4"))
    )
    (comp (ref "MOT-Z2")
      (value "KK-254-4")
      (footprint "eagle-import:MOLEX-KK-254-4")
      (libsource (lib "eagle-import") (part "KK-254-4"))
    )
    (comp (ref "PWRIN")
      (value "MSTBA2")
      (footprint "eagle-import:MSTBA2")
      (fields (field (name "MF") "FARNELL") (field (name "MPN") "1757242"))
      (libsource (lib "eagle-import") (part "MSTBA2"))
    )
    (comp (ref "Q1")
      (value "NX138BKS")
      (footprint "eagle-import:SOT363_PHILIPS")
      (libsource (lib "eagle-import") (part "NX138BKS"))
    )
    (comp (ref "Q2")
      (value "NX138BKS")
      (footprint "eagle-import:SOT363_PHILIPS")
      (libsource (lib "eagle-import") (part "NX138BKS"))
    )
    (comp (ref "Q3")
      (value "AON7524")
      (footprint "eagle-import:3X3DFN-EP")
      (libsource (lib "eagle-import") (part "AON7524"))
    )
    (comp (ref "Q4")
      (value "AON7524")
      (footprint "eagle-import:3X3DFN-EP")
      (libsource (lib "eagle-import") (part "AON7524"))
    )
    (comp (ref "R1")
      (value "47K")
      (footprint "eagle-import:R0603")
      (libsource (lib "eagle-import") (part "R-US_R0603"))
    )
    (comp (ref "R2")
      (value "4.7K")
      (footprint "eagle-import:R0603")
      (libsource (lib "eagle-import") (part "R-US_R0603"))
    )
    (comp (ref "R3")
      (value "100K")
      (footprint "eagle-import:R0603")
      (libsource (lib "eagle-import") (part "R-US_R0603"))
    )
    (comp (ref "R4")
      (value "0R1")
      (footprint "eagle-import:R0603")
      (libsource (lib "eagle-import") (part "R-US_R0603"))
    )
    (comp (ref "R5")
      (value "0R1")
      (footprint "eagle-import:R0603")
      (libsource (lib "eagle-import") (part "R-US_R0603"))
    )
    (comp (ref "R6")
      (value "3K92")
      (footprint "eagle-import:R0603")
      (libsource (lib "eagle-import") (part "R-US_R0603"))
    )
    (comp (ref "R7")
      (value "750R")
      (footprint "eagle-import:R0603")
      (libsource (lib "eagle-import") (part "R-US_R0603"))
    )
    (comp (ref "R8")
      (value "4K7")
      (footprint "eagle-import:R0603")
      (libsource (lib "eagle-import") (part "R-US_R0603"))
    )
    (comp (ref "R9")
      (value "2K2")
      (footprint "eagle-import:R0603")
      (libsource (lib "eagle-import") (part "R-US_R0603"))
    )
    (comp (ref "R10")
      (value "180R")
      (footprint "eagle-import:R0603")
      (libsource (lib "eagle-import") (part "R-US_R0603"))
    )
    (comp (ref "R11")
      (value "2K2")
      (footprint "eagle-import:R0603")
      (libsource (lib "eagle-import") (part "R-US_R0603"))
    )
    (comp (ref "R12")
      (value "27K")
      (footprint "eagle-import:R0603")
      (libsource (lib "eagle-import") (part "R-US_R0603"))
    )
    (comp (ref "R13")
      (value "47K")
      (footprint "eagle-import:R0603")
      (libsource (lib "eagle-import") (part "R-US_R0603"))
    )
    (comp (ref "R14")
      (value "10K")
      (footprint "eagle-import:R0603")
      (libsource (lib "eagle-import") (part "R-US_R0603"))
    )
    (comp (ref "R15")
      (value "1R")
      (footprint "eagle-import:R0603")
      (libsource (lib "eagle-import") (part "R-US_R0603"))
    )
    (comp (ref "R16")
      (value "10K")
      (footprint "eagle-import:R0603")
      (libsource (lib "eagle-import") (part "R-US_R0603"))
    )
    (comp (ref "R17")
      (value "4K7")
      (footprint "eagle-import:R0603")
      (libsource (lib "eagle-import") (part "R-US_R0603"))
    )
    (comp (ref "R18")
      (value "470R")
      (footprint "eagle-import:R0603")
      (libsource (lib "eagle-import") (part "R-US_R0603"))
    )
    (comp (ref "R19")
      (value "47R")
      (footprint "eagle-import:R0603")
      (libsource (lib "eagle-import") (part "R-US_R0603"))
    )
    (comp (ref "R20")
      (value "47R")
      (footprint "eagle-import:R0603")
      (libsource (lib "eagle-import") (part "R-US_R0603"))
    )
    (comp (ref "R21")
      (value "47R")
      (footprint "eagle-import:R0603")
      (libsource (lib "eagle-import") (part "R-US_R0603"))
    )
    (comp (ref "R22")
      (value "2K2")
      (footprint "eagle-import:R0603")
      (libsource (lib "eagle-import") (part "R-US_R0603"))
    )
    (comp (ref "R23")
      (value "2K2")
      (footprint "eagle-import:R0603")
      (libsource (lib "eagle-import") (part "R-US_R0603"))
    )
    (comp (ref "R24")
      (value "470R")
      (footprint "eagle-import:R0603")
      (libsource (lib "eagle-import") (part "R-US_R0603"))
    )
    (comp (ref "R25")
      (value "2K2")
      (footprint "eagle-import:R0603")
      (libsource (lib "eagle-import") (part "R-US_R0603"))
    )
    (comp (ref "R26")
      (value "2K2")
      (footprint "eagle-import:R0603")
      (libsource (lib "eagle-import") (part "R-US_R0603"))
    )
    (comp (ref "R27")
      (value "220R")
      (footprint "eagle-import:R0603")
      (libsource (lib "eagle-import") (part "R-US_R0603"))
    )
    (comp (ref "R28")
      (value "220R")
      (footprint "eagle-import:R0603")
      (libsource (lib "eagle-import") (part "R-US_R0603"))
    )
    (comp (ref "R29")
      (value "220R")
      (footprint "eagle-import:R0603")
      (libsource (lib "eagle-import") (part "R-US_R0603"))
    )
    (comp (ref "R30")
      (value "100R")
      (footprint "eagle-import:R0603")
      (libsource (lib "eagle-import") (part "R-US_R0603"))
    )
    (comp (ref "R31")
      (value "220R")
      (footprint "eagle-import:R0603")
      (libsource (lib "eagle-import") (part "R-US_R0603"))
    )
    (comp (ref "R32")
      (value "220R")
      (footprint "eagle-import:R0603")
      (libsource (lib "eagle-import") (part "R-US_R0603"))
    )
    (comp (ref "R33")
      (value "220R")
      (footprint "eagle-import:R0603")
      (libsource (lib "eagle-import") (part "R-US_R0603"))
    )
    (comp (ref "R34")
      (value "10K")
      (footprint "eagle-import:R0603")
      (libsource (lib "eagle-import") (part "R-US_R0603"))
    )
    (comp (ref "R35")
      (value "10K")
      (footprint "eagle-import:R0603")
      (libsource (lib "eagle-import") (part "R-US_R0603"))
    )
    (comp (ref "R36")
      (value "10K")
      (footprint "eagle-import:R0603")
      (libsource (lib "eagle-import") (part "R-US_R0603"))
    )
    (comp (ref "R37")
      (value "10K")
      (footprint "eagle-import:R0603")
      (libsource (lib "eagle-import") (part "R-US_R0603"))
    )
    (comp (ref "R38")
      (value "10K")
      (footprint "eagle-import:R0603")
      (libsource (lib "eagle-import") (part "R-US_R0603"))
    )
    (comp (ref "R39")
      (value "10K")
      (footprint "eagle-import:R0603")
      (libsource (lib "eagle-import") (part "R-US_R0603"))
    )
    (comp (ref "R40")
      (value "10K")
      (footprint "eagle-import:R0603")
      (libsource (lib "eagle-import") (part "R-US_R0603"))
    )
    (comp (ref "R41")
      (value "10K")
      (footprint "eagle-import:R0603")
      (libsource (lib "eagle-import") (part "R-US_R0603"))
    )
    (comp (ref "R42")
      (value "10K")
      (footprint "eagle-import:R0603")
      (libsource (lib "eagle-import") (part "R-US_R0603"))
    )
    (comp (ref "R43")
      (value "10K")
      (footprint "eagle-import:R0603")
      (libsource (lib "eagle-import") (part "R-US_R0603"))
    )
    (comp (ref "R44")
      (value "10K")
      (footprint "eagle-import:R0603")
      (libsource (lib "eagle-import") (part "R-US_R0603"))
    )
    (comp (ref "R45")
      (value "4K7 0.1%")
      (footprint "eagle-import:R0603")
      (libsource (lib "eagle-import") (part "R-US_R0603"))
    )
    (comp (ref "R46")
      (value "4K7 0.1%")
      (footprint "eagle-import:R0603")
      (libsource (lib "eagle-import") (part "R-US_R0603"))
    )
    (comp (ref "R47")
      (value "4K7 0.1%")
      (footprint "eagle-import:R0603")
      (libsource (lib "eagle-import") (part "R-US_R0603"))
    )
    (comp (ref "R48")
      (value "1K")
      (footprint "eagle-import:R0603")
      (libsource (lib "eagle-import") (part "R-US_R0603"))
    )
    (comp (ref "R49")
      (value "1K")
      (footprint "eagle-import:R0603")
      (libsource (lib "eagle-import") (part "R-US_R0603"))
    )
    (comp (ref "R50")
      (value "1K")
      (footprint "eagle-import:R0603")
      (libsource (lib "eagle-import") (part "R-US_R0603"))
    )
    (comp (ref "R51")
      (value "1K")
      (footprint "eagle-import:R0603")
      (libsource (lib "eagle-import") (part "R-US_R0603"))
    )
    (comp (ref "R52")
      (value "180R")
      (footprint "eagle-import:R0603")
      (libsource (lib "eagle-import") (part "R-US_R0603"))
    )
    (comp (ref "R53")
      (value "180R")
      (footprint "eagle-import:R0603")
      (libsource (lib "eagle-import") (part "R-US_R0603"))
    )
    (comp (ref "R54")
      (value "4K7")
      (footprint "eagle-import:R0603")
      (libsource (lib "eagle-import") (part "R-US_R0603"))
    )
    (comp (ref "R55")
      (value "4K7")
      (footprint "eagle-import:R0603")
      (libsource (lib "eagle-import") (part "R-US_R0603"))
    )
    (comp (ref "R56")
      (value "180R")
      (footprint "eagle-import:R0603")
      (libsource (lib "eagle-import") (part "R-US_R0603"))
    )
    (comp (ref "R57")
      (value "4K7")
      (footprint "eagle-import:R0603")
      (libsource (lib "eagle-import") (part "R-US_R0603"))
    )
    (comp (ref "R58")
      (value "0R11")
      (footprint "eagle-import:R1206")
      (libsource (lib "eagle-import") (part "R-US_R1206"))
    )
    (comp (ref "R59")
      (value "0R11")
      (footprint "eagle-import:R1206")
      (libsource (lib "eagle-import") (part "R-US_R1206"))
    )
    (comp (ref "R60")
      (value "20K")
      (footprint "eagle-import:RTRIM3103")
      (libsource (lib "eagle-import") (part "R-TRIMM3103"))
    )
    (comp (ref "R61")
      (value "20K")
      (footprint "eagle-import:R0603")
      (libsource (lib "eagle-import") (part "R-US_R0603"))
    )
    (comp (ref "R62")
      (value "0R11")
      (footprint "eagle-import:R1206")
      (libsource (lib "eagle-import") (part "R-US_R1206"))
    )
    (comp (ref "R63")
      (value "0R11")
      (footprint "eagle-import:R1206")
      (libsource (lib "eagle-import") (part "R-US_R1206"))
    )
    (comp (ref "R64")
      (value "20K")
      (footprint "eagle-import:RTRIM3103")
      (libsource (lib "eagle-import") (part "R-TRIMM3103"))
    )
    (comp (ref "R65")
      (value "20K")
      (footprint "eagle-import:R0603")
      (libsource (lib "eagle-import") (part "R-US_R0603"))
    )
    (comp (ref "R66")
      (value "0R11")
      (footprint "eagle-import:R1206")
      (libsource (lib "eagle-import") (part "R-US_R1206"))
    )
    (comp (ref "R67")
      (value "0R11")
      (footprint "eagle-import:R1206")
      (libsource (lib "eagle-import") (part "R-US_R1206"))
    )
    (comp (ref "R68")
      (value "20K")
      (footprint "eagle-import:RTRIM3103")
      (libsource (lib "eagle-import") (part "R-TRIMM3103"))
    )
    (comp (ref "R69")
      (value "20K")
      (footprint "eagle-import:R0603")
      (libsource (lib "eagle-import") (part "R-US_R0603"))
    )
    (comp (ref "R70")
      (value "0R11")
      (footprint "eagle-import:R1206")
      (libsource (lib "eagle-import") (part "R-US_R1206"))
    )
    (comp (ref "R71")
      (value "0R11")
      (footprint "eagle-import:R1206")
      (libsource (lib "eagle-import") (part "R-US_R1206"))
    )
    (comp (ref "R72")
      (value "20K")
      (footprint "eagle-import:RTRIM3103")
      (libsource (lib "eagle-import") (part "R-TRIMM3103"))
    )
    (comp (ref "R73")
      (value "20K")
      (footprint "eagle-import:R0603")
      (libsource (lib "eagle-import") (part "R-US_R0603"))
    )
    (comp (ref "R74")
      (value "0R11")
      (footprint "eagle-import:R1206")
      (libsource (lib "eagle-import") (part "R-US_R1206"))
    )
    (comp (ref "R75")
      (value "0R11")
      (footprint "eagle-import:R1206")
      (libsource (lib "eagle-import") (part "R-US_R1206"))
    )
    (comp (ref "R76")
      (value "20K")
      (footprint "eagle-import:RTRIM3103")
      (libsource (lib "eagle-import") (part "R-TRIMM3103"))
    )
    (comp (ref "R77")
      (value "20K")
      (footprint "eagle-import:R0603")
      (libsource (lib "eagle-import") (part "R-US_R0603"))
    )
    (comp (ref "RESET")
      (value "EVQQ2")
      (footprint "eagle-import:EVQQ2")
      (libsource (lib "eagle-import") (part "EVQQ2"))
    )
    (comp (ref "USB")
      (value "USB-B_TH")
      (footprint "eagle-import:PN61729")
      (libsource (lib "eagle-import") (part "PN61729"))
    )
    (comp (ref "USB_L")
      (value "LEDCHIPLED_0805")
      (footprint "eagle-import:CHIPLED_0805")
      (libsource (lib "eagle-import") (part "LEDCHIPLED_0805"))
    )
    (comp (ref "VIN")
      (value "LEDCHIPLED_0805")
      (footprint "eagle-import:CHIPLED_0805")
      (libsource (lib "eagle-import") (part "LEDCHIPLED_0805"))
    )
    (comp (ref "X1")
      (value "12MHz")
      (footprint "eagle-import:5.0X3.2_KX-9A")
      (libsource (lib "eagle-import") (part "CRYSTAL-4PIN"))
    )
    (comp (ref "X_STOP")
      (value "KK-254-3")
      (footprint "eagle-import:MOLEX-KK-254-3")
      (libsource (lib "eagle-import") (part "KK-254-3"))
    )
    (comp (ref "Y_STOP")
      (value "KK-254-3")
      (footprint "eagle-import:MOLEX-KK-254-3")
      (libsource (lib "eagle-import") (part "KK-254-3"))
    )
    (comp (ref "Z_STOP")
      (value "KK-254-3")
      (footprint "eagle-import:MOLEX-KK-254-3")
      (libsource (lib "eagle-import") (part "KK-254-3"))
    )
  )
  (nets
    (net (code "1") (name "+3V3") (class "Default")
      (node (ref "+3V3") (pin "A") (pinfunction "A_A") (pintype "passive"))
      (node (ref "C101") (pin "1") (pinfunction "1_1") (pintype "passive"))
      (node (ref "C114") (pin "1") (pinfunction "1_1") (pintype "passive"))
      (node (ref "C13") (pin "+") (pinfunction "+_+") (pintype "passive"))
      (node (ref "C14") (pin "1") (pinfunction "1_1") (pintype "passive"))
      (node (ref "C16") (pin "2") (pinfunction "2_2") (pintype "passive"))
      (node (ref "C17") (pin "2") (pinfunction "2_2") (pintype "passive"))
      (node (ref "C18") (pin "2") (pinfunction "2_2") (pintype "passive"))
      (node (ref "C19") (pin "2") (pinfunction "2_2") (pintype "passive"))
      (node (ref "C20") (pin "2") (pinfunction "2_2") (pintype "passive"))
      (node (ref "C21") (pin "2") (pinfunction "2_2") (pintype "passive"))
      (node (ref "C23") (pin "1") (pinfunction "1_1") (pintype "passive"))
      (node (ref "C25") (pin "1") (pinfunction "1_1") (pintype "passive"))
      (node (ref "C38") (pin "1") (pinfunction "1_1") (pintype "passive"))
      (node (ref "C39") (pin "1") (pinfunction "1_1") (pintype "passive"))
      (node (ref "C40") (pin "1") (pinfunction "1_1") (pintype "passive"))
      (node (ref "C47") (pin "1") (pinfunction "1_1") (pintype "passive"))
      (node (ref "C49") (pin "1") (pinfunction "1_1") (pintype "passive"))
      (node (ref "C62") (pin "1") (pinfunction "1_1") (pintype "passive"))
      (node (ref "C75") (pin "1") (pinfunction "1_1") (pintype "passive"))
      (node (ref "C88") (pin "1") (pinfunction "1_1") (pintype "passive"))
      (node (ref "D4") (pin "3") (pinfunction "C_3") (pintype "passive"))
      (node (ref "D5") (pin "3") (pinfunction "C_3") (pintype "passive"))
      (node (ref "D6") (pin "3") (pinfunction "C_3") (pintype "passive"))
      (node (ref "ERASE") (pin "1") (pinfunction "1_1") (pintype "passive"))
      (node (ref "IC10") (pin "10") (pinfunction "VCC_IO_10") (pintype "bidirectional"))
      (node (ref "IC11") (pin "14") (pinfunction "VCC_14") (pintype "power_in"))
      (node (ref "IC2") (pin "2") (pinfunction "VO_2") (pintype "passive"))
      (node (ref "IC2") (pin "4") (pinfunction "VO_4") (pintype "passive"))
      (node (ref "IC3") (pin "10") (pinfunction "VDDIN_10") (pintype "bidirectional"))
      (node (ref "IC3") (pin "27") (pinfunction "VDDIO-27_27") (pintype "bidirectional"))
      (node (ref "IC3") (pin "50") (pinfunction "VDDIO-50_50") (pintype "bidirectional"))
      (node (ref "IC3") (pin "69") (pinfunction "VDDIO-69_69") (pintype "bidirectional"))
      (node (ref "IC3") (pin "91") (pinfunction "VDDIO-91_91") (pintype "bidirectional"))
      (node (ref "IC3") (pin "98") (pinfunction "VDDIO-98_98") (pintype "bidirectional"))
      (node (ref "IC4") (pin "14") (pinfunction "VCC_14") (pintype "power_in"))
      (node (ref "IC6") (pin "10") (pinfunction "VCC_IO_10") (pintype "bidirectional"))
      (node (ref "IC7") (pin "10") (pinfunction "VCC_IO_10") (pintype "bidirectional"))
      (node (ref "IC8") (pin "10") (pinfunction "VCC_IO_10") (pintype "bidirectional"))
      (node (ref "IC9") (pin "10") (pinfunction "VCC_IO_10") (pintype "bidirectional"))
      (node (ref "J1") (pin "P4") (pinfunction "VDD_P4") (pintype "power_in"))
      (node (ref "L4") (pin "2") (pinfunction "2_2") (pintype "passive"))
      (node (ref "L6") (pin "1") (pinfunction "1_1") (pintype "passive"))
      (node (ref "R16") (pin "2") (pinfunction "2_2") (pintype "passive"))
      (node (ref "R34") (pin "2") (pinfunction "2_2") (pintype "passive"))
      (node (ref "R35") (pin "2") (pinfunction "2_2") (pintype "passive"))
      (node (ref "R39") (pin "2") (pinfunction "2_2") (pintype "passive"))
      (node (ref "R40") (pin "2") (pinfunction "2_2") (pintype "passive"))
      (node (ref "R41") (pin "2") (pinfunction "2_2") (pintype "passive"))
      (node (ref "X_STOP") (pin "2") (pinfunction "S_2") (pintype "passive"))
      (node (ref "Y_STOP") (pin "2") (pinfunction "S_2") (pintype "passive"))
      (node (ref "Z_STOP") (pin "2") (pinfunction "S_2") (pintype "passive"))
    )
    (net (code "2") (name "+5V") (class "Default")
      (node (ref "+5V") (pin "A") (pinfunction "A_A") (pintype "passive"))
      (node (ref "C102") (pin "1") (pinfunction "1_1") (pintype "passive"))
      (node (ref "C11") (pin "+") (pinfunction "+_+") (pintype "passive"))
      (node (ref "C12") (pin "1") (pinfunction "1_1") (pintype "passive"))
      (node (ref "C48") (pin "1") (pinfunction "1_1") (pintype "passive"))
      (node (ref "C50") (pin "1") (pinfunction "1_1") (pintype "passive"))
      (node (ref "C63") (pin "1") (pinfunction "1_1") (pintype "passive"))
      (node (ref "C76") (pin "1") (pinfunction "1_1") (pintype "passive"))
      (node (ref "C89") (pin "1") (pinfunction "1_1") (pintype "passive"))
      (node (ref "EXP2") (pin "10") (pinfunction "S_10") (pintype "passive"))
      (node (ref "IC10") (pin "34") (pinfunction "VCC_34") (pintype "bidirectional"))
      (node (ref "IC2") (pin "3") (pinfunction "VI_3") (pintype "input"))
      (node (ref "IC5") (pin "14") (pinfunction "VCC_14") (pintype "power_in"))
      (node (ref "IC6") (pin "34") (pinfunction "VCC_34") (pintype "bidirectional"))
      (node (ref "IC7") (pin "34") (pinfunction "VCC_34") (pintype "bidirectional"))
      (node (ref "IC8") (pin "34") (pinfunction "VCC_34") (pintype "bidirectional"))
      (node (ref "IC9") (pin "34") (pinfunction "VCC_34") (pintype "bidirectional"))
      (node (ref "L3") (pin "2") (pinfunction "2_2") (pintype "passive"))
      (node (ref "R61") (pin "2") (pinfunction "2_2") (pintype "passive"))
      (node (ref "R65") (pin "2") (pinfunction "2_2") (pintype "passive"))
      (node (ref "R69") (pin "2") (pinfunction "2_2") (pintype "passive"))
      (node (ref "R73") (pin "2") (pinfunction "2_2") (pintype "passive"))
      (node (ref "R77") (pin "2") (pinfunction "2_2") (pintype "passive"))
    )
    (net (code "3") (name "+12V") (class "Default")
      (node (ref "C104") (pin "2") (pinfunction "2_2") (pintype "passive"))
      (node (ref "C105") (pin "1") (pinfunction "1_1") (pintype "passive"))
      (node (ref "C107") (pin "+") (pinfunction "+_+") (pintype "passive"))
      (node (ref "C108") (pin "1") (pinfunction "1_1") (pintype "passive"))
      (node (ref "C109") (pin "1") (pinfunction "1_1") (pintype "passive"))
      (node (ref "C52") (pin "2") (pinfunction "2_2") (pintype "passive"))
      (node (ref "C53") (pin "1") (pinfunction "1_1") (pintype "passive"))
      (node (ref "C55") (pin "+") (pinfunction "+_+") (pintype "passive"))
      (node (ref "C56") (pin "1") (pinfunction "1_1") (pintype "passive"))
      (node (ref "C57") (pin "1") (pinfunction "1_1") (pintype "passive"))
      (node (ref "C65") (pin "2") (pinfunction "2_2") (pintype "passive"))
      (node (ref "C66") (pin "1") (pinfunction "1_1") (pintype "passive"))
      (node (ref "C68") (pin "+") (pinfunction "+_+") (pintype "passive"))
      (node (ref "C69") (pin "1") (pinfunction "1_1") (pintype "passive"))
      (node (ref "C70") (pin "1") (pinfunction "1_1") (pintype "passive"))
      (node (ref "C78") (pin "2") (pinfunction "2_2") (pintype "passive"))
      (node (ref "C79") (pin "1") (pinfunction "1_1") (pintype "passive"))
      (node (ref "C81") (pin "+") (pinfunction "+_+") (pintype "passive"))
      (node (ref "C82") (pin "1") (pinfunction "1_1") (pintype "passive"))
      (node (ref "C83") (pin "1") (pinfunction "1_1") (pintype "passive"))
      (node (ref "C91") (pin "2") (pinfunction "2_2") (pintype "passive"))
      (node (ref "C92") (pin "1") (pinfunction "1_1") (pintype "passive"))
      (node (ref "C94") (pin "+") (pinfunction "+_+") (pintype "passive"))
      (node (ref "C95") (pin "1") (pinfunction "1_1") (pintype "passive"))
      (node (ref "C96") (pin "1") (pinfunction "1_1") (pintype "passive"))
      (node (ref "D1") (pin "A") (pinfunction "A_A") (pintype "passive"))
      (node (ref "F2") (pin "1") (pinfunction "1_1") (pintype "passive"))
      (node (ref "F3") (pin "1") (pinfunction "1_1") (pintype "passive"))
      (node (ref "FAN1") (pin "1") (pinfunction "S_1") (pintype "passive"))
      (node (ref "FAN2") (pin "1") (pinfunction "S_1") (pintype "passive"))
      (node (ref "FAN3") (pin "1") (pinfunction "S_1") (pintype "passive"))
      (node (ref "FAN4") (pin "1") (pinfunction "S_1") (pintype "passive"))
      (node (ref "IC10") (pin "21") (pinfunction "VS_21") (pintype "bidirectional"))
      (node (ref "IC10") (pin "39") (pinfunction "VSA_39") (pintype "bidirectional"))
      (node (ref "IC10") (pin "40") (pinfunction "VS_40") (pintype "bidirectional"))
      (node (ref "IC6") (pin "21") (pinfunction "VS_21") (pintype "bidirectional"))
      (node (ref "IC6") (pin "39") (pinfunction "VSA_39") (pintype "bidirectional"))
      (node (ref "IC6") (pin "40") (pinfunction "VS_40") (pintype "bidirectional"))
      (node (ref "IC7") (pin "21") (pinfunction "VS_21") (pintype "bidirectional"))
      (node (ref "IC7") (pin "39") (pinfunction "VSA_39") (pintype "bidirectional"))
      (node (ref "IC7") (pin "40") (pinfunction "VS_40") (pintype "bidirectional"))
      (node (ref "IC8") (pin "21") (pinfunction "VS_21") (pintype "bidirectional"))
      (node (ref "IC8") (pin "39") (pinfunction "VSA_39") (pintype "bidirectional"))
      (node (ref "IC8") (pin "40") (pinfunction "VS_40") (pintype "bidirectional"))
      (node (ref "IC9") (pin "21") (pinfunction "VS_21") (pintype "bidirectional"))
      (node (ref "IC9") (pin "39") (pinfunction "VSA_39") (pintype "bidirectional"))
      (node (ref "IC9") (pin "40") (pinfunction "VS_40") (pintype "bidirectional"))
      (node (ref "PWRIN") (pin "1") (pinfunction "1_1") (pintype "passive"))
      (node (ref "R1") (pin "2") (pinfunction "2_2") (pintype "passive"))
      (node (ref "VIN") (pin "A") (pinfunction "A_A") (pintype "passive"))
    )
    (net (code "4") (name "/ADVREF") (class "Default")
      (node (ref "C24") (pin "1") (pinfunction "1_1") (pintype "passive"))
      (node (ref "IC3") (pin "1") (pinfunction "ADVREF_1") (pintype "bidirectional"))
      (node (ref "L4") (pin "1") (pinfunction "1_1") (pintype "passive"))
      (node (ref "R45") (pin "2") (pinfunction "2_2") (pintype "passive"))
      (node (ref "R46") (pin "2") (pinfunction "2_2") (pintype "passive"))
      (node (ref "R47") (pin "2") (pinfunction "2_2") (pintype "passive"))
    )
    (net (code "5") (name "/BED") (class "Default")
      (node (ref "IC3") (pin "86") (pinfunction "PC22_86") (pintype "bidirectional"))
      (node (ref "R56") (pin "1") (pinfunction "1_1") (pintype "passive"))
    )
    (net (code "6") (name "/E1_DIR") (class "Default")
      (node (ref "IC3") (pin "51") (pinfunction "TDI/PB4_51") (pintype "bidirectional"))
      (node (ref "IC6") (pin "9") (pinfunction "REFR_DIR_9") (pintype "bidirectional"))
    )
    (net (code "7") (name "/E1_EN") (class "Default")
      (node (ref "IC3") (pin "55") (pinfunction "PA4/PGMNCMD_55") (pintype "bidirectional"))
      (node (ref "IC6") (pin "3") (pinfunction "CSN_CFG3_3") (pintype "bidirectional"))
    )
    (net (code "8") (name "/E1_STEP") (class "Default")
      (node (ref "IC3") (pin "54") (pinfunction "PC28_54") (pintype "bidirectional"))
      (node (ref "IC6") (pin "8") (pinfunction "REFL_STEP_8") (pintype "bidirectional"))
    )
    (net (code "9") (name "/E2_DIR") (class "Default")
      (node (ref "IC3") (pin "62") (pinfunction "PC9_62") (pintype "bidirectional"))
      (node (ref "IC7") (pin "9") (pinfunction "REFR_DIR_9") (pintype "bidirectional"))
    )
    (net (code "10") (name "/E2_EN") (class "Default")
      (node (ref "IC3") (pin "66") (pinfunction "PA3_66") (pintype "bidirectional"))
      (node (ref "IC7") (pin "3") (pinfunction "CSN_CFG3_3") (pintype "bidirectional"))
    )
    (net (code "11") (name "/E2_STEP") (class "Default")
      (node (ref "IC3") (pin "65") (pinfunction "PC10_65") (pintype "bidirectional"))
      (node (ref "IC7") (pin "8") (pinfunction "REFL_STEP_8") (pintype "bidirectional"))
    )
    (net (code "12") (name "/ENN") (class "Default")
      (node (ref "IC10") (pin "29") (pinfunction "DRV_ENN_CFG6_29") (pintype "bidirectional"))
      (node (ref "IC3") (pin "25") (pinfunction "PC0_25") (pintype "bidirectional"))
      (node (ref "IC6") (pin "29") (pinfunction "DRV_ENN_CFG6_29") (pintype "bidirectional"))
      (node (ref "IC7") (pin "29") (pinfunction "DRV_ENN_CFG6_29") (pintype "bidirectional"))
      (node (ref "IC8") (pin "29") (pinfunction "DRV_ENN_CFG6_29") (pintype "bidirectional"))
      (node (ref "IC9") (pin "29") (pinfunction "DRV_ENN_CFG6_29") (pintype "bidirectional"))
    )
    (net (code "13") (name "/ESP_DATA_RDY") (class "Default")
      (node (ref "IC3") (pin "73") (pinfunction "PC16_73") (pintype "bidirectional"))
      (node (ref "R25") (pin "1") (pinfunction "1_1") (pintype "passive"))
    )
    (net (code "14") (name "/ESP_EN") (class "Default")
      (node (ref "ESP8266") (pin "3") (pinfunction "CH_PD_3") (pintype "input"))
      (node (ref "IC3") (pin "71") (pinfunction "PC14_71") (pintype "bidirectional"))
      (node (ref "R17") (pin "1") (pinfunction "1_1") (pintype "passive"))
    )
    (net (code "15") (name "/ESP_MISO") (class "Default")
      (node (ref "IC3") (pin "41") (pinfunction "PA12/PGMD0_41") (pintype "bidirectional"))
      (node (ref "R20") (pin "2") (pinfunction "2_2") (pintype "passive"))
    )
    (net (code "16") (name "/ESP_MOSI") (class "Default")
      (node (ref "IC3") (pin "33") (pinfunction "PA13/PGMD1_33") (pintype "bidirectional"))
      (node (ref "R21") (pin "2") (pinfunction "2_2") (pintype "passive"))
    )
    (net (code "17") (name "/ESP_NPCS0") (class "Default")
      (node (ref "IC3") (pin "42") (pinfunction "PA11/PGMM3_42") (pintype "bidirectional"))
      (node (ref "R26") (pin "1") (pinfunction "1_1") (pintype "passive"))
    )
    (net (code "18") (name "/ESP_RESET") (class "Default")
      (node (ref "IC3") (pin "32") (pinfunction "PC6_32") (pintype "bidirectional"))
      (node (ref "R18") (pin "1") (pinfunction "1_1") (pintype "passive"))
    )
    (net (code "19") (name "/ESP_SCK") (class "Default")
      (node (ref "IC3") (pin "31") (pinfunction "PA14/PGMD2_31") (pintype "bidirectional"))
      (node (ref "R19") (pin "2") (pinfunction "2_2") (pintype "passive"))
    )
    (net (code "20") (name "/ESP_URXD") (class "Default")
      (node (ref "IC3") (pin "46") (pinfunction "PA9/PGMM1_46") (pintype "bidirectional"))
      (node (ref "R23") (pin "1") (pinfunction "1_1") (pintype "passive"))
    )
    (net (code "21") (name "/ESP_UTXD") (class "Default")
      (node (ref "IC3") (pin "44") (pinfunction "PA10/PGMM2_44") (pintype "bidirectional"))
      (node (ref "R24") (pin "1") (pinfunction "1_1") (pintype "passive"))
    )
    (net (code "22") (name "/EXT1") (class "Default")
      (node (ref "IC3") (pin "40") (pinfunction "PC3_40") (pintype "bidirectional"))
      (node (ref "R52") (pin "1") (pinfunction "1_1") (pintype "passive"))
    )
    (net (code "23") (name "/EXT2") (class "Default")
      (node (ref "IC3") (pin "19") (pinfunction "PC15/AD11_19") (pintype "bidirectional"))
      (node (ref "R53") (pin "1") (pinfunction "1_1") (pintype "passive"))
    )
    (net (code "24") (name "/FAN_1") (class "Default")
      (node (ref "IC3") (pin "76") (pinfunction "TDO/TRACESWO/PB5_76") (pintype "bidirectional"))
      (node (ref "R48") (pin "1") (pinfunction "1_1") (pintype "passive"))
    )
    (net (code "25") (name "/FAN_2") (class "Default")
      (node (ref "IC3") (pin "43") (pinfunction "PC2_43") (pintype "bidirectional"))
      (node (ref "R49") (pin "1") (pinfunction "1_1") (pintype "passive"))
    )
    (net (code "26") (name "/FAN_3") (class "Default")
      (node (ref "IC3") (pin "14") (pinfunction "PA18/PGMD6/AD1_14") (pintype "bidirectional"))
      (node (ref "R50") (pin "1") (pinfunction "1_1") (pintype "passive"))
    )
    (net (code "27") (name "/FAN_4") (class "Default")
      (node (ref "IC3") (pin "74") (pinfunction "PA0/PGMEN0_74") (pintype "bidirectional"))
      (node (ref "R51") (pin "1") (pinfunction "1_1") (pintype "passive"))
    )
    (net (code "28") (name "/LCD_BEEP") (class "Default")
      (node (ref "EXP2") (pin "1") (pinfunction "S_1") (pintype "passive"))
      (node (ref "IC3") (pin "75") (pinfunction "PC17_75") (pintype "bidirectional"))
      (node (ref "R57") (pin "2") (pinfunction "2_2") (pintype "passive"))
    )
    (net (code "29") (name "/LCD_CS") (class "Default")
      (node (ref "IC3") (pin "80") (pinfunction "PC19_80") (pintype "bidirectional"))
      (node (ref "IC5") (pin "10") (pinfunction "I1_10") (pintype "input"))
      (node (ref "IC5") (pin "12") (pinfunction "I0_12") (pintype "input"))
      (node (ref "IC5") (pin "5") (pinfunction "I1_5") (pintype "input"))
      (node (ref "IC5") (pin "9") (pinfunction "I0_9") (pintype "input"))
    )
    (net (code "30") (name "/LCD_ENC_A") (class "Default")
      (node (ref "EXP1") (pin "5") (pinfunction "S_5") (pintype "passive"))
      (node (ref "IC3") (pin "83") (pinfunction "TCK/SWCLK/PB7_83") (pintype "bidirectional"))
    )
    (net (code "31") (name "/LCD_ENC_B") (class "Default")
      (node (ref "EXP1") (pin "3") (pinfunction "S_3") (pintype "passive"))
      (node (ref "IC3") (pin "82") (pinfunction "PC20_82") (pintype "bidirectional"))
    )
    (net (code "32") (name "/LCD_ENC_SW") (class "Default")
      (node (ref "EXP2") (pin "2") (pinfunction "S_2") (pintype "passive"))
      (node (ref "IC3") (pin "84") (pinfunction "PC21_84") (pintype "bidirectional"))
    )
    (net (code "33") (name "/LCD_MISO") (class "Default")
      (node (ref "IC3") (pin "53") (pinfunction "PA5/PGMRDY_53") (pintype "bidirectional"))
      (node (ref "IC4") (pin "6") (pinfunction "O_6") (pintype "tri_state"))
    )
    (net (code "34") (name "/LCD_MISO_BUF") (class "Default")
      (node (ref "EXP1") (pin "1") (pinfunction "S_1") (pintype "passive"))
      (node (ref "IC4") (pin "5") (pinfunction "I_5") (pintype "input"))
    )
    (net (code "35") (name "/LCD_MOSI") (class "Default")
      (node (ref "IC3") (pin "52") (pinfunction "PB6/PGMNOE_52") (pintype "bidirectional"))
      (node (ref "IC4") (pin "9") (pinfunction "I_9") (pintype "input"))
      (node (ref "IC5") (pin "4") (pinfunction "I0_4") (pintype "input"))
    )
    (net (code "36") (name "/LCD_MOSI_BUF") (class "Default")
      (node (ref "EXP2") (pin "3") (pinfunction "S_3") (pintype "passive"))
      (node (ref "IC5") (pin "6") (pinfunction "O_6") (pintype "output"))
    )
    (net (code "37") (name "/LCD_SCK") (class "Default")
      (node (ref "IC3") (pin "67") (pinfunction "PA2/PGMEN2_67") (pintype "bidirectional"))
      (node (ref "IC4") (pin "12") (pinfunction "I_12") (pintype "input"))
      (node (ref "IC5") (pin "13") (pinfunction "I1_13") (pintype "input"))
    )
    (net (code "38") (name "/LCD_SCK_BUF") (class "Default")
      (node (ref "EXP2") (pin "5") (pinfunction "S_5") (pintype "passive"))
      (node (ref "IC5") (pin "11") (pinfunction "O_11") (pintype "output"))
    )
    (net (code "39") (name "/LCD_SD_CS") (class "Default")
      (node (ref "EXP1") (pin "4") (pinfunction "S_4") (pintype "passive"))
      (node (ref "IC3") (pin "99") (pinfunction "PB14/DAC1_99") (pintype "bidirectional"))
      (node (ref "IC4") (pin "4") (pinfunction "OE_4") (pintype "input"))
    )
    (net (code "40") (name "/MCCDA") (class "Default")
      (node (ref "IC3") (pin "59") (pinfunction "PA28_59") (pintype "bidirectional"))
      (node (ref "R29") (pin "1") (pinfunction "1_1") (pintype "passive"))
    )
    (net (code "41") (name "/MCCK") (class "Default")
      (node (ref "IC3") (pin "63") (pinfunction "PA29_63") (pintype "bidirectional"))
      (node (ref "R30") (pin "1") (pinfunction "1_1") (pintype "passive"))
    )
    (net (code "42") (name "/MCDA0") (class "Default")
      (node (ref "IC3") (pin "64") (pinfunction "PA30_64") (pintype "bidirectional"))
      (node (ref "R28") (pin "1") (pinfunction "1_1") (pintype "passive"))
    )
    (net (code "43") (name "/MCDA1") (class "Default")
      (node (ref "IC3") (pin "81") (pinfunction "PA31_81") (pintype "bidirectional"))
      (node (ref "R32") (pin "1") (pinfunction "1_1") (pintype "passive"))
    )
    (net (code "44") (name "/MCDA2") (class "Default")
      (node (ref "IC3") (pin "39") (pinfunction "PA26/PGMD14_39") (pintype "bidirectional"))
      (node (ref "R33") (pin "1") (pinfunction "1_1") (pintype "passive"))
    )
    (net (code "45") (name "/MCDA3") (class "Default")
      (node (ref "IC3") (pin "57") (pinfunction "PA27/PGMD15_57") (pintype "bidirectional"))
      (node (ref "R31") (pin "1") (pinfunction "1_1") (pintype "passive"))
    )
    (net (code "46") (name "/MOT_MISO") (class "Default")
      (node (ref "IC10") (pin "7") (pinfunction "SDO_NAO_CFG0_7") (pintype "bidirectional"))
      (node (ref "IC3") (pin "15") (pinfunction "PA21/PGMD9/AD8_15") (pintype "bidirectional"))
      (node (ref "IC6") (pin "7") (pinfunction "SDO_NAO_CFG0_7") (pintype "bidirectional"))
      (node (ref "IC7") (pin "7") (pinfunction "SDO_NAO_CFG0_7") (pintype "bidirectional"))
      (node (ref "IC8") (pin "7") (pinfunction "SDO_NAO_CFG0_7") (pintype "bidirectional"))
      (node (ref "IC9") (pin "7") (pinfunction "SDO_NAO_CFG0_7") (pintype "bidirectional"))
    )
    (net (code "47") (name "/MOT_MOSI") (class "Default")
      (node (ref "IC10") (pin "5") (pinfunction "SDI_NAI_CFG1_5") (pintype "bidirectional"))
      (node (ref "IC3") (pin "20") (pinfunction "PA22/PGMD10/AD9_20") (pintype "bidirectional"))
      (node (ref "IC6") (pin "5") (pinfunction "SDI_NAI_CFG1_5") (pintype "bidirectional"))
      (node (ref "IC7") (pin "5") (pinfunction "SDI_NAI_CFG1_5") (pintype "bidirectional"))
      (node (ref "IC8") (pin "5") (pinfunction "SDI_NAI_CFG1_5") (pintype "bidirectional"))
      (node (ref "IC9") (pin "5") (pinfunction "SDI_NAI_CFG1_5") (pintype "bidirectional"))
    )
    (net (code "48") (name "/MOT_SCK") (class "Default")
      (node (ref "IC10") (pin "4") (pinfunction "SCK_CFG2_4") (pintype "bidirectional"))
      (node (ref "IC3") (pin "22") (pinfunction "PA23/PGMD11_22") (pintype "bidirectional"))
      (node (ref "IC6") (pin "4") (pinfunction "SCK_CFG2_4") (pintype "bidirectional"))
      (node (ref "IC7") (pin "4") (pinfunction "SCK_CFG2_4") (pintype "bidirectional"))
      (node (ref "IC8") (pin "4") (pinfunction "SCK_CFG2_4") (pintype "bidirectional"))
      (node (ref "IC9") (pin "4") (pinfunction "SCK_CFG2_4") (pintype "bidirectional"))
    )
    (net (code "49") (name "/PWR_FAIL_DET2") (class "Default")
      (node (ref "C1") (pin "1") (pinfunction "1_1") (pintype "passive"))
      (node (ref "IC3") (pin "6") (pinfunction "PC30/AD14_6") (pintype "bidirectional"))
      (node (ref "R1") (pin "1") (pinfunction "1_1") (pintype "passive"))
      (node (ref "R2") (pin "2") (pinfunction "2_2") (pintype "passive"))
    )
    (net (code "50") (name "/RESET") (class "Default")
      (node (ref "C35") (pin "1") (pinfunction "1_1") (pintype "passive"))
      (node (ref "IC3") (pin "60") (pinfunction "NRST_60") (pintype "bidirectional"))
      (node (ref "R16") (pin "1") (pinfunction "1_1") (pintype "passive"))
      (node (ref "RESET") (pin "A'") (pinfunction "P1_A'") (pintype "passive"))
    )
    (net (code "51") (name "/SAM_TFR_RDY") (class "Default")
      (node (ref "ESP8266") (pin "14") (pinfunction "GPIO4_14") (pintype "bidirectional"))
      (node (ref "IC3") (pin "72") (pinfunction "PA1/PGMEN1_72") (pintype "bidirectional"))
    )
    (net (code "52") (name "/SD_CD") (class "Default")
      (node (ref "IC3") (pin "58") (pinfunction "PC8_58") (pintype "bidirectional"))
      (node (ref "R27") (pin "1") (pinfunction "1_1") (pintype "passive"))
    )
    (net (code "53") (name "/SG_TST") (class "Default")
      (node (ref "IC11") (pin "6") (pinfunction "O_6") (pintype "output"))
      (node (ref "IC3") (pin "49") (pinfunction "PA7/XIN32/PGMNVALID_49") (pintype "bidirectional"))
    )
    (net (code "54") (name "/SG_TST_E1") (class "Default")
      (node (ref "IC11") (pin "12") (pinfunction "I0_12") (pintype "input"))
      (node (ref "IC6") (pin "27") (pinfunction "SWP_DIAG1_27") (pintype "bidirectional"))
    )
    (net (code "55") (name "/SG_TST_E2") (class "Default")
      (node (ref "IC11") (pin "9") (pinfunction "I0_9") (pintype "input"))
      (node (ref "IC7") (pin "27") (pinfunction "SWP_DIAG1_27") (pintype "bidirectional"))
    )
    (net (code "56") (name "/SG_TST_X") (class "Default")
      (node (ref "IC11") (pin "13") (pinfunction "I1_13") (pintype "input"))
      (node (ref "IC8") (pin "27") (pinfunction "SWP_DIAG1_27") (pintype "bidirectional"))
    )
    (net (code "57") (name "/SG_TST_Y") (class "Default")
      (node (ref "IC11") (pin "1") (pinfunction "I0_1") (pintype "input"))
      (node (ref "IC9") (pin "27") (pinfunction "SWP_DIAG1_27") (pintype "bidirectional"))
    )
    (net (code "58") (name "/SG_TST_Z") (class "Default")
      (node (ref "IC10") (pin "27") (pinfunction "SWP_DIAG1_27") (pintype "bidirectional"))
      (node (ref "IC11") (pin "2") (pinfunction "I1_2") (pintype "input"))
    )
    (net (code "59") (name "/T_BED") (class "Default")
      (node (ref "C46") (pin "1") (pinfunction "1_1") (pintype "passive"))
      (node (ref "IC3") (pin "5") (pinfunction "PB1/AD5_5") (pintype "bidirectional"))
      (node (ref "R42") (pin "1") (pinfunction "1_1") (pintype "passive"))
    )
    (net (code "60") (name "/T_EXT1") (class "Default")
      (node (ref "C45") (pin "1") (pinfunction "1_1") (pintype "passive"))
      (node (ref "IC3") (pin "3") (pinfunction "PB0/AD4_3") (pintype "bidirectional"))
      (node (ref "R43") (pin "1") (pinfunction "1_1") (pintype "passive"))
    )
    (net (code "61") (name "/T_EXT2") (class "Default")
      (node (ref "C44") (pin "1") (pinfunction "1_1") (pintype "passive"))
      (node (ref "IC3") (pin "4") (pinfunction "PC29/AD13_4") (pintype "bidirectional"))
      (node (ref "R44") (pin "1") (pinfunction "1_1") (pintype "passive"))
    )
    (net (code "62") (name "/USB_N") (class "Default")
      (node (ref "D3") (pin "3") (pinfunction "3_3") (pintype "bidirectional"))
      (node (ref "IC3") (pin "88") (pinfunction "DDM/PB10_88") (pintype "bidirectional"))
      (node (ref "USB") (pin "2") (pinfunction "2_2") (pintype "bidirectional"))
    )
    (net (code "63") (name "/USB_P") (class "Default")
      (node (ref "D3") (pin "2") (pinfunction "2_2") (pintype "bidirectional"))
      (node (ref "IC3") (pin "89") (pinfunction "DDP/PB11_89") (pintype "bidirectional"))
      (node (ref "USB") (pin "3") (pinfunction "3_3") (pintype "bidirectional"))
    )
    (net (code "64") (name "/USB_PWR_MON") (class "Default")
      (node (ref "C15") (pin "2") (pinfunction "2_2") (pintype "passive"))
      (node (ref "IC3") (pin "68") (pinfunction "PC11_68") (pintype "bidirectional"))
      (node (ref "R12") (pin "2") (pinfunction "2_2") (pintype "passive"))
      (node (ref "R13") (pin "1") (pinfunction "1_1") (pintype "passive"))
    )
    (net (code "65") (name "/VBUS") (class "Default")
      (node (ref "D3") (pin "4") (pinfunction "4_4") (pintype "bidirectional"))
      (node (ref "R12") (pin "1") (pinfunction "1_1") (pintype "passive"))
      (node (ref "USB") (pin "1") (pinfunction "1_1") (pintype "bidirectional"))
      (node (ref "USB_L") (pin "A") (pinfunction "A_A") (pintype "passive"))
    )
    (net (code "66") (name "/VREF_MON") (class "Default")
      (node (ref "IC3") (pin "12") (pinfunction "PA17/PGMD5/AD0_12") (pintype "bidirectional"))
    )
    (net (code "67") (name "/VSSA") (class "Default")
      (node (ref "BED") (pin "2") (pinfunction "S_2") (pintype "passive"))
      (node (ref "C22") (pin "1") (pinfunction "1_1") (pintype "passive"))
      (node (ref "EXT1") (pin "2") (pinfunction "S_2") (pintype "passive"))
      (node (ref "EXT2") (pin "2") (pinfunction "S_2") (pintype "passive"))
      (node (ref "F1") (pin "1") (pinfunction "1_1") (pintype "passive"))
      (node (ref "R14") (pin "2") (pinfunction "2_2") (pintype "passive"))
    )
    (net (code "68") (name "/VSSA_MON") (class "Default")
      (node (ref "IC3") (pin "18") (pinfunction "PA19/PGMD7/AD2_18") (pintype "bidirectional"))
      (node (ref "R14") (pin "1") (pinfunction "1_1") (pintype "passive"))
    )
    (net (code "69") (name "/X_DIR") (class "Default")
      (node (ref "IC3") (pin "21") (pinfunction "PC13/AD10_21") (pintype "bidirectional"))
      (node (ref "IC8") (pin "9") (pinfunction "REFR_DIR_9") (pintype "bidirectional"))
    )
    (net (code "70") (name "/X_EN") (class "Default")
      (node (ref "IC3") (pin "24") (pinfunction "PA20/PGMD8/AD3_24") (pintype "bidirectional"))
      (node (ref "IC8") (pin "3") (pinfunction "CSN_CFG3_3") (pintype "bidirectional"))
    )
    (net (code "71") (name "/X_STEP") (class "Default")
      (node (ref "IC3") (pin "23") (pinfunction "PC12/AD12_23") (pintype "bidirectional"))
      (node (ref "IC8") (pin "8") (pinfunction "REFL_STEP_8") (pintype "bidirectional"))
    )
    (net (code "72") (name "/X_STOP") (class "Default")
      (node (ref "C41") (pin "1") (pinfunction "1_1") (pintype "passive"))
      (node (ref "D4") (pin "1") (pinfunction "A_1") (pintype "passive"))
      (node (ref "IC3") (pin "30") (pinfunction "PA15/PGMD3_30") (pintype "bidirectional"))
      (node (ref "R36") (pin "1") (pinfunction "1_1") (pintype "passive"))
    )
    (net (code "73") (name "/Y_DIR") (class "Default")
      (node (ref "IC3") (pin "34") (pinfunction "PA24/PGMD12_34") (pintype "bidirectional"))
      (node (ref "IC9") (pin "9") (pinfunction "REFR_DIR_9") (pintype "bidirectional"))
    )
    (net (code "74") (name "/Y_EN") (class "Default")
      (node (ref "IC3") (pin "37") (pinfunction "PC4_37") (pintype "bidirectional"))
      (node (ref "IC9") (pin "3") (pinfunction "CSN_CFG3_3") (pintype "bidirectional"))
    )
    (net (code "75") (name "/Y_STEP") (class "Default")
      (node (ref "IC3") (pin "35") (pinfunction "PC5_35") (pintype "bidirectional"))
      (node (ref "IC9") (pin "8") (pinfunction "REFL_STEP_8") (pintype "bidirectional"))
    )
    (net (code "76") (name "/Y_STOP") (class "Default")
      (node (ref "C42") (pin "1") (pinfunction "1_1") (pintype "passive"))
      (node (ref "D5") (pin "1") (pinfunction "A_1") (pintype "passive"))
      (node (ref "IC3") (pin "29") (pinfunction "PC7_29") (pintype "bidirectional"))
      (node (ref "R37") (pin "1") (pinfunction "1_1") (pintype "passive"))
    )
    (net (code "77") (name "/Z_DIR") (class "Default")
      (node (ref "IC10") (pin "9") (pinfunction "REFR_DIR_9") (pintype "bidirectional"))
      (node (ref "IC3") (pin "38") (pinfunction "PA25/PGMD13_38") (pintype "bidirectional"))
    )
    (net (code "78") (name "/Z_EN") (class "Default")
      (node (ref "IC10") (pin "3") (pinfunction "CSN_CFG3_3") (pintype "bidirectional"))
      (node (ref "IC3") (pin "48") (pinfunction "PA8/XOUT32/PGMM0_48") (pintype "bidirectional"))
    )
    (net (code "79") (name "/Z_STEP") (class "Default")
      (node (ref "IC10") (pin "8") (pinfunction "REFL_STEP_8") (pintype "bidirectional"))
      (node (ref "IC3") (pin "47") (pinfunction "PC1_47") (pintype "bidirectional"))
    )
    (net (code "80") (name "/Z_STOP") (class "Default")
      (node (ref "C43") (pin "1") (pinfunction "1_1") (pintype "passive"))
      (node (ref "D6") (pin "1") (pinfunction "A_1") (pintype "passive"))
      (node (ref "IC3") (pin "28") (pinfunction "PA16/PGMD4_28") (pintype "bidirectional"))
      (node (ref "R38") (pin "1") (pinfunction "1_1") (pintype "passive"))
    )
    (net (code "81") (name "GND") (class "Default")
      (node (ref "BEDOUT") (pin "2") (pinfunction "S_2") (pintype "passive"))
      (node (ref "C1") (pin "2") (pinfunction "2_2") (pintype "passive"))
      (node (ref "C100") (pin "2") (pinfunction "2_2") (pintype "passive"))
      (node (ref "C101") (pin "2") (pinfunction "2_2") (pintype "passive"))
      (node (ref "C102") (pin "2") (pinfunction "2_2") (pintype "passive"))
      (node (ref "C103") (pin "2") (pinfunction "2_2") (pintype "passive"))
      (node (ref "C104") (pin "1") (pinfunction "1_1") (pintype "passive"))
      (node (ref "C107") (pin "-") (pinfunction "-_-") (pintype "passive"))
      (node (ref "C108") (pin "2") (pinfunction "2_2") (pintype "passive"))
      (node (ref "C109") (pin "2") (pinfunction "2_2") (pintype "passive"))
      (node (ref "C11") (pin "-") (pinfunction "-_-") (pintype "passive"))
      (node (ref "C110") (pin "2") (pinfunction "2_2") (pintype "passive"))
      (node (ref "C111") (pin "2") (pinfunction "2_2") (pintype "passive"))
      (node (ref "C112") (pin "2") (pinfunction "2_2") (pintype "passive"))
      (node (ref "C113") (pin "2") (pinfunction "2_2") (pintype "passive"))
      (node (ref "C114") (pin "2") (pinfunction "2_2") (pintype "passive"))
      (node (ref "C12") (pin "2") (pinfunction "2_2") (pintype "passive"))
      (node (ref "C13") (pin "-") (pinfunction "-_-") (pintype "passive"))
      (node (ref "C14") (pin "2") (pinfunction "2_2") (pintype "passive"))
      (node (ref "C15") (pin "1") (pinfunction "1_1") (pintype "passive"))
      (node (ref "C16") (pin "1") (pinfunction "1_1") (pintype "passive"))
      (node (ref "C17") (pin "1") (pinfunction "1_1") (pintype "passive"))
      (node (ref "C18") (pin "1") (pinfunction "1_1") (pintype "passive"))
      (node (ref "C19") (pin "1") (pinfunction "1_1") (pintype "passive"))
      (node (ref "C2") (pin "2") (pinfunction "2_2") (pintype "passive"))
      (node (ref "C20") (pin "1") (pinfunction "1_1") (pintype "passive"))
      (node (ref "C21") (pin "1") (pinfunction "1_1") (pintype "passive"))
      (node (ref "C22") (pin "2") (pinfunction "2_2") (pintype "passive"))
      (node (ref "C23") (pin "2") (pinfunction "2_2") (pintype "passive"))
      (node (ref "C24") (pin "2") (pinfunction "2_2") (pintype "passive"))
      (node (ref "C25") (pin "2") (pinfunction "2_2") (pintype "passive"))
      (node (ref "C26") (pin "2") (pinfunction "2_2") (pintype "passive"))
      (node (ref "C27") (pin "2") (pinfunction "2_2") (pintype "passive"))
      (node (ref "C28") (pin "2") (pinfunction "2_2") (pintype "passive"))
      (node (ref "C29") (pin "2") (pinfunction "2_2") (pintype "passive"))
      (node (ref "C3") (pin "-") (pinfunction "-_-") (pintype "passive"))
      (node (ref "C30") (pin "2") (pinfunction "2_2") (pintype "passive"))
      (node (ref "C31") (pin "2") (pinfunction "2_2") (pintype "passive"))
      (node (ref "C32") (pin "2") (pinfunction "2_2") (pintype "passive"))
      (node (ref "C33") (pin "2") (pinfunction "2_2") (pintype "passive"))
      (node (ref "C34") (pin "2") (pinfunction "2_2") (pintype "passive"))
      (node (ref "C35") (pin "2") (pinfunction "2_2") (pintype "passive"))
      (node (ref "C36") (pin "2") (pinfunction "2_2") (pintype "passive"))
      (node (ref "C37") (pin "2") (pinfunction "2_2") (pintype "passive"))
      (node (ref "C38") (pin "2") (pinfunction "2_2") (pintype "passive"))
      (node (ref "C39") (pin "2") (pinfunction "2_2") (pintype "passive"))
      (node (ref "C4") (pin "2") (pinfunction "2_2") (pintype "passive"))
      (node (ref "C40") (pin "2") (pinfunction "2_2") (pintype "passive"))
      (node (ref "C41") (pin "2") (pinfunction "2_2") (pintype "passive"))
      (node (ref "C42") (pin "2") (pinfunction "2_2") (pintype "passive"))
      (node (ref "C43") (pin "2") (pinfunction "2_2") (pintype "passive"))
      (node (ref "C44") (pin "2") (pinfunction "2_2") (pintype "passive"))
      (node (ref "C45") (pin "2") (pinfunction "2_2") (pintype "passive"))
      (node (ref "C46") (pin "2") (pinfunction "2_2") (pintype "passive"))
      (node (ref "C47") (pin "2") (pinfunction "2_2") (pintype "passive"))
      (node (ref "C48") (pin "2") (pinfunction "2_2") (pintype "passive"))
      (node (ref "C49") (pin "2") (pinfunction "2_2") (pintype "passive"))
      (node (ref "C5") (pin "-") (pinfunction "-_-") (pintype "passive"))
      (node (ref "C50") (pin "2") (pinfunction "2_2") (pintype "passive"))
      (node (ref "C51") (pin "2") (pinfunction "2_2") (pintype "passive"))
      (node (ref "C52") (pin "1") (pinfunction "1_1") (pintype "passive"))
      (node (ref "C55") (pin "-") (pinfunction "-_-") (pintype "passive"))
      (node (ref "C56") (pin "2") (pinfunction "2_2") (pintype "passive"))
      (node (ref "C57") (pin "2") (pinfunction "2_2") (pintype "passive"))
      (node (ref "C58") (pin "2") (pinfunction "2_2") (pintype "passive"))
      (node (ref "C59") (pin "2") (pinfunction "2_2") (pintype "passive"))
      (node (ref "C6") (pin "2") (pinfunction "2_2") (pintype "passive"))
      (node (ref "C60") (pin "2") (pinfunction "2_2") (pintype "passive"))
      (node (ref "C61") (pin "2") (pinfunction "2_2") (pintype "passive"))
      (node (ref "C62") (pin "2") (pinfunction "2_2") (pintype "passive"))
      (node (ref "C63") (pin "2") (pinfunction "2_2") (pintype "passive"))
      (node (ref "C64") (pin "2") (pinfunction "2_2") (pintype "passive"))
      (node (ref "C65") (pin "1") (pinfunction "1_1") (pintype "passive"))
      (node (ref "C68") (pin "-") (pinfunction "-_-") (pintype "passive"))
      (node (ref "C69") (pin "2") (pinfunction "2_2") (pintype "passive"))
      (node (ref "C70") (pin "2") (pinfunction "2_2") (pintype "passive"))
      (node (ref "C71") (pin "2") (pinfunction "2_2") (pintype "passive"))
      (node (ref "C72") (pin "2") (pinfunction "2_2") (pintype "passive"))
      (node (ref "C73") (pin "2") (pinfunction "2_2") (pintype "passive"))
      (node (ref "C74") (pin "2") (pinfunction "2_2") (pintype "passive"))
      (node (ref "C75") (pin "2") (pinfunction "2_2") (pintype "passive"))
      (node (ref "C76") (pin "2") (pinfunction "2_2") (pintype "passive"))
      (node (ref "C77") (pin "2") (pinfunction "2_2") (pintype "passive"))
      (node (ref "C78") (pin "1") (pinfunction "1_1") (pintype "passive"))
      (node (ref "C8") (pin "2") (pinfunction "2_2") (pintype "passive"))
      (node (ref "C81") (pin "-") (pinfunction "-_-") (pintype "passive"))
      (node (ref "C82") (pin "2") (pinfunction "2_2") (pintype "passive"))
      (node (ref "C83") (pin "2") (pinfunction "2_2") (pintype "passive"))
      (node (ref "C84") (pin "2") (pinfunction "2_2") (pintype "passive"))
      (node (ref "C85") (pin "2") (pinfunction "2_2") (pintype "passive"))
      (node (ref "C86") (pin "2") (pinfunction "2_2") (pintype "passive"))
      (node (ref "C87") (pin "2") (pinfunction "2_2") (pintype "passive"))
      (node (ref "C88") (pin "2") (pinfunction "2_2") (pintype "passive"))
      (node (ref "C89") (pin "2") (pinfunction "2_2") (pintype "passive"))
      (node (ref "C9") (pin "2") (pinfunction "2_2") (pintype "passive"))
      (node (ref "C90") (pin "2") (pinfunction "2_2") (pintype "passive"))
      (node (ref "C91") (pin "1") (pinfunction "1_1") (pintype "passive"))
      (node (ref "C94") (pin "-") (pinfunction "-_-") (pintype "passive"))
      (node (ref "C95") (pin "2") (pinfunction "2_2") (pintype "passive"))
      (node (ref "C96") (pin "2") (pinfunction "2_2") (pintype "passive"))
      (node (ref "C97") (pin "2") (pinfunction "2_2") (pintype "passive"))
      (node (ref "C98") (pin "2") (pinfunction "2_2") (pintype "passive"))
      (node (ref "C99") (pin "2") (pinfunction "2_2") (pintype "passive"))
      (node (ref "D3") (pin "1") (pinfunction "1_1") (pintype "bidirectional"))
      (node (ref "ESP8266") (pin "9") (pinfunction "GND_9") (pintype "power_in"))
      (node (ref "EXP1") (pin "9") (pinfunction "S_9") (pintype "passive"))
      (node (ref "EXP2") (pin "9") (pinfunction "S_9") (pintype "passive"))
      (node (ref "F1") (pin "2") (pinfunction "2_2") (pintype "passive"))
      (node (ref "IC1") (pin "10") (pinfunction "DIS_10") (pintype "bidirectional"))
      (node (ref "IC1") (pin "13") (pinfunction "NC13_13") (pintype "bidirectional"))
      (node (ref "IC1") (pin "14") (pinfunction "NC14_14") (pintype "bidirectional"))
      (node (ref "IC1") (pin "15") (pinfunction "NC15_15") (pintype "bidirectional"))
      (node (ref "IC1") (pin "16") (pinfunction "NC16_16") (pintype "bidirectional"))
      (node (ref "IC1") (pin "2") (pinfunction "NC2_2") (pintype "bidirectional"))
      (node (ref "IC1") (pin "6") (pinfunction "GND_6") (pintype "bidirectional"))
      (node (ref "IC1") (pin "7") (pinfunction "NC7_7") (pintype "bidirectional"))
      (node (ref "IC1") (pin "EXP") (pinfunction "PAD_EXP") (pintype "bidirectional"))
      (node (ref "IC10") (pin "1") (pinfunction "TST_MODE_1") (pintype "bidirectional"))
      (node (ref "IC10") (pin "13") (pinfunction "GNDP_13") (pintype "bidirectional"))
      (node (ref "IC10") (pin "2") (pinfunction "CLK_2") (pintype "bidirectional"))
      (node (ref "IC10") (pin "24") (pinfunction "ENCB_DCEN_CFG4_24") (pintype "bidirectional"))
      (node (ref "IC10") (pin "31") (pinfunction "GND_31") (pintype "bidirectional"))
      (node (ref "IC10") (pin "32") (pinfunction "GNDA_32") (pintype "bidirectional"))
      (node (ref "IC10") (pin "36") (pinfunction "GND_36") (pintype "bidirectional"))
      (node (ref "IC10") (pin "48") (pinfunction "GNDP_48") (pintype "bidirectional"))
      (node (ref "IC10") (pin "6") (pinfunction "GND_6") (pintype "bidirectional"))
      (node (ref "IC10") (pin "PAD") (pinfunction "GND_PAD_PAD") (pintype "bidirectional"))
      (node (ref "IC11") (pin "7") (pinfunction "GND_7") (pintype "power_in"))
      (node (ref "IC2") (pin "1") (pinfunction "GND_1") (pintype "passive"))
      (node (ref "IC3") (pin "2") (pinfunction "GND-2_2") (pintype "bidirectional"))
      (node (ref "IC3") (pin "26") (pinfunction "GND-26_26") (pintype "bidirectional"))
      (node (ref "IC3") (pin "45") (pinfunction "GND-45_45") (pintype "bidirectional"))
      (node (ref "IC3") (pin "61") (pinfunction "TST_61") (pintype "bidirectional"))
      (node (ref "IC3") (pin "70") (pinfunction "GND-70_70") (pintype "bidirectional"))
      (node (ref "IC3") (pin "77") (pinfunction "JTAGSEL_77") (pintype "bidirectional"))
      (node (ref "IC3") (pin "95") (pinfunction "GND-95_95") (pintype "bidirectional"))
      (node (ref "IC4") (pin "1") (pinfunction "OE_1") (pintype "input"))
      (node (ref "IC4") (pin "10") (pinfunction "OE_10") (pintype "input"))
      (node (ref "IC4") (pin "13") (pinfunction "OE_13") (pintype "input"))
      (node (ref "IC4") (pin "2") (pinfunction "I_2") (pintype "input"))
      (node (ref "IC4") (pin "7") (pinfunction "GND_7") (pintype "power_in"))
      (node (ref "IC5") (pin "1") (pinfunction "I0_1") (pintype "input"))
      (node (ref "IC5") (pin "2") (pinfunction "I1_2") (pintype "input"))
      (node (ref "IC5") (pin "7") (pinfunction "GND_7") (pintype "power_in"))
      (node (ref "IC5") (pin "EXP") (pinfunction "GND_EXP") (pintype "power_in"))
      (node (ref "IC6") (pin "1") (pinfunction "TST_MODE_1") (pintype "bidirectional"))
      (node (ref "IC6") (pin "13") (pinfunction "GNDP_13") (pintype "bidirectional"))
      (node (ref "IC6") (pin "2") (pinfunction "CLK_2") (pintype "bidirectional"))
      (node (ref "IC6") (pin "24") (pinfunction "ENCB_DCEN_CFG4_24") (pintype "bidirectional"))
      (node (ref "IC6") (pin "31") (pinfunction "GND_31") (pintype "bidirectional"))
      (node (ref "IC6") (pin "32") (pinfunction "GNDA_32") (pintype "bidirectional"))
      (node (ref "IC6") (pin "36") (pinfunction "GND_36") (pintype "bidirectional"))
      (node (ref "IC6") (pin "48") (pinfunction "GNDP_48") (pintype "bidirectional"))
      (node (ref "IC6") (pin "6") (pinfunction "GND_6") (pintype "bidirectional"))
      (node (ref "IC6") (pin "PAD") (pinfunction "GND_PAD_PAD") (pintype "bidirectional"))
      (node (ref "IC7") (pin "1") (pinfunction "TST_MODE_1") (pintype "bidirectional"))
      (node (ref "IC7") (pin "13") (pinfunction "GNDP_13") (pintype "bidirectional"))
      (node (ref "IC7") (pin "2") (pinfunction "CLK_2") (pintype "bidirectional"))
      (node (ref "IC7") (pin "24") (pinfunction "ENCB_DCEN_CFG4_24") (pintype "bidirectional"))
      (node (ref "IC7") (pin "31") (pinfunction "GND_31") (pintype "bidirectional"))
      (node (ref "IC7") (pin "32") (pinfunction "GNDA_32") (pintype "bidirectional"))
      (node (ref "IC7") (pin "36") (pinfunction "GND_36") (pintype "bidirectional"))
      (node (ref "IC7") (pin "48") (pinfunction "GNDP_48") (pintype "bidirectional"))
      (node (ref "IC7") (pin "6") (pinfunction "GND_6") (pintype "bidirectional"))
      (node (ref "IC7") (pin "PAD") (pinfunction "GND_PAD_PAD") (pintype "bidirectional"))
      (node (ref "IC8") (pin "1") (pinfunction "TST_MODE_1") (pintype "bidirectional"))
      (node (ref "IC8") (pin "13") (pinfunction "GNDP_13") (pintype "bidirectional"))
      (node (ref "IC8") (pin "2") (pinfunction "CLK_2") (pintype "bidirectional"))
      (node (ref "IC8") (pin "24") (pinfunction "ENCB_DCEN_CFG4_24") (pintype "bidirectional"))
      (node (ref "IC8") (pin "31") (pinfunction "GND_31") (pintype "bidirectional"))
      (node (ref "IC8") (pin "32") (pinfunction "GNDA_32") (pintype "bidirectional"))
      (node (ref "IC8") (pin "36") (pinfunction "GND_36") (pintype "bidirectional"))
      (node (ref "IC8") (pin "48") (pinfunction "GNDP_48") (pintype "bidirectional"))
      (node (ref "IC8") (pin "6") (pinfunction "GND_6") (pintype "bidirectional"))
      (node (ref "IC8") (pin "PAD") (pinfunction "GND_PAD_PAD") (pintype "bidirectional"))
      (node (ref "IC9") (pin "1") (pinfunction "TST_MODE_1") (pintype "bidirectional"))
      (node (ref "IC9") (pin "13") (pinfunction "GNDP_13") (pintype "bidirectional"))
      (node (ref "IC9") (pin "2") (pinfunction "CLK_2") (pintype "bidirectional"))
      (node (ref "IC9") (pin "24") (pinfunction "ENCB_DCEN_CFG4_24") (pintype "bidirectional"))
      (node (ref "IC9") (pin "31") (pinfunction "GND_31") (pintype "bidirectional"))
      (node (ref "IC9") (pin "32") (pinfunction "GNDA_32") (pintype "bidirectional"))
      (node (ref "IC9") (pin "36") (pinfunction "GND_36") (pintype "bidirectional"))
      (node (ref "IC9") (pin "48") (pinfunction "GNDP_48") (pintype "bidirectional"))
      (node (ref "IC9") (pin "6") (pinfunction "GND_6") (pintype "bidirectional"))
      (node (ref "IC9") (pin "PAD") (pinfunction "GND_PAD_PAD") (pintype "bidirectional"))
      (node (ref "J1") (pin "G1") (pinfunction "GND_G1") (pintype "power_in"))
      (node (ref "J1") (pin "G2") (pinfunction "GND_G2") (pintype "power_in"))
      (node (ref "J1") (pin "G3") (pinfunction "GND_G3") (pintype "power_in"))
      (node (ref "J1") (pin "G4") (pinfunction "GND_G4") (pintype "power_in"))
      (node (ref "J1") (pin "P6") (pinfunction "VSS_P6") (pintype "power_in"))
      (node (ref "PWRIN") (pin "2") (pinfunction "1_2") (pintype "passive"))
      (node (ref "Q1") (pin "1") (pinfunction "S_1") (pintype "passive"))
      (node (ref "Q1") (pin "4") (pinfunction "S_4") (pintype "passive"))
      (node (ref "Q2") (pin "1") (pinfunction "S_1") (pintype "passive"))
      (node (ref "Q2") (pin "4") (pinfunction "S_4") (pintype "passive"))
      (node (ref "Q3") (pin "1") (pinfunction "S_1") (pintype "passive"))
      (node (ref "Q3") (pin "2") (pinfunction "S_2") (pintype "passive"))
      (node (ref "Q3") (pin "3") (pinfunction "S_3") (pintype "passive"))
      (node (ref "Q4") (pin "1") (pinfunction "S_1") (pintype "passive"))
      (node (ref "Q4") (pin "2") (pinfunction "S_2") (pintype "passive"))
      (node (ref "Q4") (pin "3") (pinfunction "S_3") (pintype "passive"))
      (node (ref "R10") (pin "2") (pinfunction "2_2") (pintype "passive"))
      (node (ref "R11") (pin "2") (pinfunction "2_2") (pintype "passive"))
      (node (ref "R13") (pin "2") (pinfunction "2_2") (pintype "passive"))
      (node (ref "R17") (pin "2") (pinfunction "2_2") (pintype "passive"))
      (node (ref "R2") (pin "1") (pinfunction "1_1") (pintype "passive"))
      (node (ref "R22") (pin "1") (pinfunction "1_1") (pintype "passive"))
      (node (ref "R57") (pin "1") (pinfunction "1_1") (pintype "passive"))
      (node (ref "R58") (pin "2") (pinfunction "2_2") (pintype "passive"))
      (node (ref "R59") (pin "2") (pinfunction "2_2") (pintype "passive"))
      (node (ref "R60") (pin "1") (pinfunction "A_1") (pintype "passive"))
      (node (ref "R62") (pin "2") (pinfunction "2_2") (pintype "passive"))
      (node (ref "R63") (pin "2") (pinfunction "2_2") (pintype "passive"))
      (node (ref "R64") (pin "1") (pinfunction "A_1") (pintype "passive"))
      (node (ref "R66") (pin "2") (pinfunction "2_2") (pintype "passive"))
      (node (ref "R67") (pin "2") (pinfunction "2_2") (pintype "passive"))
      (node (ref "R68") (pin "1") (pinfunction "A_1") (pintype "passive"))
      (node (ref "R7") (pin "1") (pinfunction "1_1") (pintype "passive"))
      (node (ref "R70") (pin "2") (pinfunction "2_2") (pintype "passive"))
      (node (ref "R71") (pin "2") (pinfunction "2_2") (pintype "passive"))
      (node (ref "R72") (pin "1") (pinfunction "A_1") (pintype "passive"))
      (node (ref "R74") (pin "2") (pinfunction "2_2") (pintype "passive"))
      (node (ref "R75") (pin "2") (pinfunction "2_2") (pintype "passive"))
      (node (ref "R76") (pin "1") (pinfunction "A_1") (pintype "passive"))
      (node (ref "R8") (pin "2") (pinfunction "2_2") (pintype "passive"))
      (node (ref "R9") (pin "2") (pinfunction "2_2") (pintype "passive"))
      (node (ref "RESET") (pin "B") (pinfunction "S_B") (pintype "passive"))
      (node (ref "RESET") (pin "B'") (pinfunction "S1_B'") (pintype "passive"))
      (node (ref "USB") (pin "4") (pinfunction "4_4") (pintype "bidirectional"))
      (node (ref "USB") (pin "P$1") (pinfunction "P$1_P$1") (pintype "bidirectional"))
      (node (ref "USB") (pin "P$2") (pinfunction "P$2_P$2") (pintype "bidirectional"))
      (node (ref "X1") (pin "2") (pinfunction "2_2") (pintype "passive"))
      (node (ref "X1") (pin "4") (pinfunction "4_4") (pintype "passive"))
      (node (ref "X_STOP") (pin "3") (pinfunction "S_3") (pintype "passive"))
      (node (ref "Y_STOP") (pin "3") (pinfunction "S_3") (pintype "passive"))
      (node (ref "Z_STOP") (pin "3") (pinfunction "S_3") (pintype "passive"))
    )
    (net (code "82") (name "Net-(+3V3-PadC)") (class "Default")
      (node (ref "+3V3") (pin "C") (pinfunction "C_C") (pintype "passive"))
      (node (ref "R10") (pin "1") (pinfunction "1_1") (pintype "passive"))
    )
    (net (code "83") (name "Net-(+5V-PadC)") (class "Default")
      (node (ref "+5V") (pin "C") (pinfunction "C_C") (pintype "passive"))
      (node (ref "R9") (pin "1") (pinfunction "1_1") (pintype "passive"))
    )
    (net (code "84") (name "Net-(BEDA-S)") (class "Default")
      (node (ref "BED") (pin "1") (pinfunction "S_1") (pintype "passive"))
      (node (ref "R42") (pin "2") (pinfunction "2_2") (pintype "passive"))
      (node (ref "R47") (pin "1") (pinfunction "1_1") (pintype "passive"))
    )
    (net (code "85") (name "Net-(BEDOUTA-S)") (class "Default")
      (node (ref "BEDOUT") (pin "1") (pinfunction "S_1") (pintype "passive"))
      (node (ref "R56") (pin "2") (pinfunction "2_2") (pintype "passive"))
    )
    (net (code "86") (name "Net-(C2-Pad1)") (class "Default")
      (node (ref "C2") (pin "1") (pinfunction "1_1") (pintype "passive"))
      (node (ref "C3") (pin "+") (pinfunction "+_+") (pintype "passive"))
      (node (ref "D1") (pin "C") (pinfunction "C_C") (pintype "passive"))
      (node (ref "L1") (pin "1") (pinfunction "1_1") (pintype "passive"))
    )
    (net (code "87") (name "Net-(C26-Pad1)") (class "Default")
      (node (ref "C26") (pin "1") (pinfunction "1_1") (pintype "passive"))
      (node (ref "R15") (pin "1") (pinfunction "1_1") (pintype "passive"))
    )
    (net (code "88") (name "Net-(D2-A)") (class "Default")
      (node (ref "D2") (pin "P$2") (pinfunction "A_P$2") (pintype "bidirectional"))
      (node (ref "IC1") (pin "8") (pinfunction "ISEN_8") (pintype "bidirectional"))
      (node (ref "R4") (pin "2") (pinfunction "2_2") (pintype "passive"))
      (node (ref "R5") (pin "2") (pinfunction "2_2") (pintype "passive"))
    )
    (net (code "89") (name "Net-(D2-K)") (class "Default")
      (node (ref "C7") (pin "2") (pinfunction "2_2") (pintype "passive"))
      (node (ref "D2") (pin "P$1") (pinfunction "K_P$1") (pintype "bidirectional"))
      (node (ref "IC1") (pin "12") (pinfunction "LX_12") (pintype "bidirectional"))
      (node (ref "L2") (pin "P$1") (pinfunction "1_P$1") (pintype "passive"))
    )
    (net (code "90") (name "Net-(ESP8266-GPIO0)") (class "Default")
      (node (ref "ESP8266") (pin "12") (pinfunction "GPIO0_12") (pintype "bidirectional"))
      (node (ref "R25") (pin "2") (pinfunction "2_2") (pintype "passive"))
    )
    (net (code "91") (name "Net-(ESP8266-GPIO12)") (class "Default")
      (node (ref "ESP8266") (pin "6") (pinfunction "GPIO12_6") (pintype "bidirectional"))
      (node (ref "R20") (pin "1") (pinfunction "1_1") (pintype "passive"))
    )
    (net (code "92") (name "Net-(ESP8266-GPIO13)") (class "Default")
      (node (ref "ESP8266") (pin "7") (pinfunction "GPIO13_7") (pintype "bidirectional"))
      (node (ref "R21") (pin "1") (pinfunction "1_1") (pintype "passive"))
    )
    (net (code "93") (name "Net-(ESP8266-GPIO14)") (class "Default")
      (node (ref "ESP8266") (pin "5") (pinfunction "GPIO14_5") (pintype "bidirectional"))
      (node (ref "R19") (pin "1") (pinfunction "1_1") (pintype "passive"))
    )
    (net (code "94") (name "Net-(ESP8266-GPIO15)") (class "Default")
      (node (ref "ESP8266") (pin "10") (pinfunction "GPIO15_10") (pintype "bidirectional"))
      (node (ref "R26") (pin "2") (pinfunction "2_2") (pintype "passive"))
    )
    (net (code "95") (name "Net-(ESP8266-RESET)") (class "Default")
      (node (ref "ESP8266") (pin "1") (pinfunction "RESET_1") (pintype "input"))
      (node (ref "R18") (pin "2") (pinfunction "2_2") (pintype "passive"))
      (node (ref "R22") (pin "2") (pinfunction "2_2") (pintype "passive"))
    )
    (net (code "96") (name "Net-(ESP8266-RXD)") (class "Default")
      (node (ref "ESP8266") (pin "15") (pinfunction "RXD_15") (pintype "input"))
      (node (ref "R24") (pin "2") (pinfunction "2_2") (pintype "passive"))
    )
    (net (code "97") (name "Net-(ESP8266-TXD)") (class "Default")
      (node (ref "ESP8266") (pin "16") (pinfunction "TXD_16") (pintype "output"))
      (node (ref "R23") (pin "2") (pinfunction "2_2") (pintype "passive"))
    )
    (net (code "98") (name "Net-(ESP8266-VCC)") (class "Default")
      (node (ref "ESP8266") (pin "8") (pinfunction "VCC_8") (pintype "power_in"))
      (node (ref "L6") (pin "2") (pinfunction "2_2") (pintype "passive"))
    )
    (net (code "99") (name "Net-(EXP1C-S)") (class "Default")
      (node (ref "EXP1") (pin "2") (pinfunction "S_2") (pintype "passive"))
      (node (ref "IC4") (pin "11") (pinfunction "O_11") (pintype "tri_state"))
    )
    (net (code "100") (name "Net-(EXP1G-S)") (class "Default")
      (node (ref "EXP1") (pin "6") (pinfunction "S_6") (pintype "passive"))
      (node (ref "IC4") (pin "8") (pinfunction "O_8") (pintype "tri_state"))
    )
    (net (code "101") (name "Net-(EXP2E-S)") (class "Default")
      (node (ref "EXP2") (pin "4") (pinfunction "S_4") (pintype "passive"))
      (node (ref "IC5") (pin "8") (pinfunction "O_8") (pintype "output"))
    )
    (net (code "102") (name "Net-(EXT1A-S)") (class "Default")
      (node (ref "EXT1") (pin "1") (pinfunction "S_1") (pintype "passive"))
      (node (ref "R43") (pin "2") (pinfunction "2_2") (pintype "passive"))
      (node (ref "R46") (pin "1") (pinfunction "1_1") (pintype "passive"))
    )
    (net (code "103") (name "Net-(EXT1_L-PadA)") (class "Default")
      (node (ref "EXT1_L") (pin "A") (pinfunction "A_A") (pintype "passive"))
      (node (ref "R54") (pin "1") (pinfunction "1_1") (pintype "passive"))
    )
    (net (code "104") (name "Net-(EXT1_L-PadC)") (class "Default")
      (node (ref "EXT1_L") (pin "C") (pinfunction "C_C") (pintype "passive"))
      (node (ref "J2") (pin "1") (pinfunction "1_1") (pintype "passive"))
      (node (ref "Q3") (pin "5") (pinfunction "D_5") (pintype "passive"))
      (node (ref "Q3") (pin "6") (pinfunction "D_6") (pintype "passive"))
      (node (ref "Q3") (pin "7") (pinfunction "D_7") (pintype "passive"))
      (node (ref "Q3") (pin "8") (pinfunction "D_8") (pintype "passive"))
      (node (ref "Q3") (pin "E1") (pinfunction "D_E1") (pintype "passive"))
      (node (ref "Q3") (pin "E2") (pinfunction "D_E2") (pintype "passive"))
      (node (ref "Q3") (pin "PAD") (pinfunction "D_PAD") (pintype "passive"))
    )
    (net (code "105") (name "Net-(EXT2A-S)") (class "Default")
      (node (ref "EXT2") (pin "1") (pinfunction "S_1") (pintype "passive"))
      (node (ref "R44") (pin "2") (pinfunction "2_2") (pintype "passive"))
      (node (ref "R45") (pin "1") (pinfunction "1_1") (pintype "passive"))
    )
    (net (code "106") (name "Net-(EXT2_L-PadA)") (class "Default")
      (node (ref "EXT2_L") (pin "A") (pinfunction "A_A") (pintype "passive"))
      (node (ref "R55") (pin "1") (pinfunction "1_1") (pintype "passive"))
    )
    (net (code "107") (name "Net-(FAN1B-S)") (class "Default")
      (node (ref "FAN1") (pin "2") (pinfunction "S_2") (pintype "passive"))
      (node (ref "Q1") (pin "6") (pinfunction "D_6") (pintype "passive"))
    )
    (net (code "108") (name "Net-(FAN2B-S)") (class "Default")
      (node (ref "FAN2") (pin "2") (pinfunction "S_2") (pintype "passive"))
      (node (ref "Q1") (pin "3") (pinfunction "D_3") (pintype "passive"))
    )
    (net (code "109") (name "Net-(FAN3B-S)") (class "Default")
      (node (ref "FAN3") (pin "2") (pinfunction "S_2") (pintype "passive"))
      (node (ref "Q2") (pin "6") (pinfunction "D_6") (pintype "passive"))
    )
    (net (code "110") (name "Net-(FAN4B-S)") (class "Default")
      (node (ref "FAN4") (pin "2") (pinfunction "S_2") (pintype "passive"))
      (node (ref "Q2") (pin "3") (pinfunction "D_3") (pintype "passive"))
    )
    (net (code "111") (name "Net-(IC1-BOOT)") (class "Default")
      (node (ref "C7") (pin "1") (pinfunction "1_1") (pintype "passive"))
      (node (ref "IC1") (pin "11") (pinfunction "BOOT_11") (pintype "bidirectional"))
    )
    (net (code "112") (name "Net-(IC1-FB)") (class "Default")
      (node (ref "C10") (pin "2") (pinfunction "2_2") (pintype "passive"))
      (node (ref "IC1") (pin "5") (pinfunction "FB_5") (pintype "bidirectional"))
      (node (ref "R6") (pin "1") (pinfunction "1_1") (pintype "passive"))
      (node (ref "R7") (pin "2") (pinfunction "2_2") (pintype "passive"))
    )
    (net (code "113") (name "Net-(IC1-SGND)") (class "Default")
      (node (ref "IC1") (pin "9") (pinfunction "SGND_9") (pintype "bidirectional"))
      (node (ref "R4") (pin "1") (pinfunction "1_1") (pintype "passive"))
      (node (ref "R5") (pin "1") (pinfunction "1_1") (pintype "passive"))
    )
    (net (code "114") (name "Net-(IC1-SS)") (class "Default")
      (node (ref "C6") (pin "1") (pinfunction "1_1") (pintype "passive"))
      (node (ref "IC1") (pin "4") (pinfunction "SS_4") (pintype "bidirectional"))
    )
    (net (code "115") (name "Net-(IC1-TON)") (class "Default")
      (node (ref "IC1") (pin "3") (pinfunction "TON_3") (pintype "bidirectional"))
      (node (ref "R3") (pin "1") (pinfunction "1_1") (pintype "passive"))
    )
    (net (code "116") (name "Net-(IC1-VIN)") (class "Default")
      (node (ref "C4") (pin "1") (pinfunction "1_1") (pintype "passive"))
      (node (ref "C5") (pin "+") (pinfunction "+_+") (pintype "passive"))
      (node (ref "IC1") (pin "1") (pinfunction "VIN_1") (pintype "bidirectional"))
      (node (ref "L1") (pin "2") (pinfunction "2_2") (pintype "passive"))
      (node (ref "R3") (pin "2") (pinfunction "2_2") (pintype "passive"))
    )
    (net (code "117") (name "Net-(IC3-ERASE{slash}PB12)") (class "Default")
      (node (ref "ERASE") (pin "2") (pinfunction "2_2") (pintype "passive"))
      (node (ref "IC3") (pin "87") (pinfunction "ERASE/PB12_87") (pintype "bidirectional"))
    )
    (net (code "118") (name "Net-(IC3-PB8{slash}XOUT)") (class "Default")
      (node (ref "C37") (pin "1") (pinfunction "1_1") (pintype "passive"))
      (node (ref "IC3") (pin "96") (pinfunction "PB8/XOUT_96") (pintype "bidirectional"))
      (node (ref "X1") (pin "1") (pinfunction "1_1") (pintype "passive"))
    )
    (net (code "119") (name "Net-(IC3-PB9{slash}PGMCK{slash}XIN)") (class "Default")
      (node (ref "C36") (pin "1") (pinfunction "1_1") (pintype "passive"))
      (node (ref "IC3") (pin "97") (pinfunction "PB9/PGMCK/XIN_97") (pintype "bidirectional"))
      (node (ref "X1") (pin "3") (pinfunction "3_3") (pintype "passive"))
    )
    (net (code "120") (name "Net-(IC3-VDDCORE-16)") (class "Default")
      (node (ref "C28") (pin "1") (pinfunction "1_1") (pintype "passive"))
      (node (ref "C29") (pin "1") (pinfunction "1_1") (pintype "passive"))
      (node (ref "C30") (pin "1") (pinfunction "1_1") (pintype "passive"))
      (node (ref "C31") (pin "1") (pinfunction "1_1") (pintype "passive"))
      (node (ref "C32") (pin "1") (pinfunction "1_1") (pintype "passive"))
      (node (ref "C33") (pin "1") (pinfunction "1_1") (pintype "passive"))
      (node (ref "C34") (pin "1") (pinfunction "1_1") (pintype "passive"))
      (node (ref "IC3") (pin "11") (pinfunction "VDDOUT_11") (pintype "bidirectional"))
      (node (ref "IC3") (pin "16") (pinfunction "VDDCORE-16_16") (pintype "bidirectional"))
      (node (ref "IC3") (pin "36") (pinfunction "VDDCORE-36_36") (pintype "bidirectional"))
      (node (ref "IC3") (pin "56") (pinfunction "VDDCORE-56_56") (pintype "bidirectional"))
      (node (ref "IC3") (pin "85") (pinfunction "VDDCORE-85_85") (pintype "bidirectional"))
      (node (ref "L5") (pin "2") (pinfunction "2_2") (pintype "passive"))
    )
    (net (code "121") (name "Net-(IC3-VDDPLL)") (class "Default")
      (node (ref "C27") (pin "1") (pinfunction "1_1") (pintype "passive"))
      (node (ref "IC3") (pin "100") (pinfunction "VDDPLL_100") (pintype "bidirectional"))
      (node (ref "L5") (pin "1") (pinfunction "1_1") (pintype "passive"))
      (node (ref "R15") (pin "2") (pinfunction "2_2") (pintype "passive"))
    )
    (net (code "122") (name "Net-(IC6-5VOUT)") (class "Default")
      (node (ref "C51") (pin "1") (pinfunction "1_1") (pintype "passive"))
      (node (ref "IC6") (pin "33") (pinfunction "5VOUT_33") (pintype "bidirectional"))
    )
    (net (code "123") (name "Net-(IC6-AIN_IREF)") (class "Default")
      (node (ref "IC6") (pin "30") (pinfunction "AIN_IREF_30") (pintype "bidirectional"))
      (node (ref "R60") (pin "2") (pinfunction "S_2") (pintype "passive"))
    )
    (net (code "124") (name "Net-(IC6-BRA)") (class "Default")
      (node (ref "IC6") (pin "44") (pinfunction "BRA_44") (pintype "bidirectional"))
      (node (ref "R58") (pin "1") (pinfunction "1_1") (pintype "passive"))
    )
    (net (code "125") (name "Net-(IC6-BRB)") (class "Default")
      (node (ref "IC6") (pin "17") (pinfunction "BRB_17") (pintype "bidirectional"))
      (node (ref "R59") (pin "1") (pinfunction "1_1") (pintype "passive"))
    )
    (net (code "126") (name "Net-(IC6-CPI)") (class "Default")
      (node (ref "C54") (pin "1") (pinfunction "1_1") (pintype "passive"))
      (node (ref "IC6") (pin "37") (pinfunction "CPI_37") (pintype "bidirectional"))
    )
    (net (code "127") (name "Net-(IC6-CPO)") (class "Default")
      (node (ref "C54") (pin "2") (pinfunction "2_2") (pintype "passive"))
      (node (ref "IC6") (pin "35") (pinfunction "CPO_35") (pintype "bidirectional"))
    )
    (net (code "128") (name "Net-(IC6-OA1)") (class "Default")
      (node (ref "C58") (pin "1") (pinfunction "1_1") (pintype "passive"))
      (node (ref "IC6") (pin "46") (pinfunction "OA1_46") (pintype "bidirectional"))
      (node (ref "MOT-E1") (pin "1") (pinfunction "S_1") (pintype "passive"))
    )
    (net (code "129") (name "Net-(IC6-OA2)") (class "Default")
      (node (ref "C59") (pin "1") (pinfunction "1_1") (pintype "passive"))
      (node (ref "IC6") (pin "42") (pinfunction "OA2_42") (pintype "bidirectional"))
      (node (ref "MOT-E1") (pin "2") (pinfunction "S_2") (pintype "passive"))
    )
    (net (code "130") (name "Net-(IC6-OB1)") (class "Default")
      (node (ref "C60") (pin "1") (pinfunction "1_1") (pintype "passive"))
      (node (ref "IC6") (pin "15") (pinfunction "OB1_15") (pintype "bidirectional"))
      (node (ref "MOT-E1") (pin "4") (pinfunction "S_4") (pintype "passive"))
    )
    (net (code "131") (name "Net-(IC6-OB2)") (class "Default")
      (node (ref "C61") (pin "1") (pinfunction "1_1") (pintype "passive"))
      (node (ref "IC6") (pin "19") (pinfunction "OB2_19") (pintype "bidirectional"))
      (node (ref "MOT-E1") (pin "3") (pinfunction "S_3") (pintype "passive"))
    )
    (net (code "132") (name "Net-(IC6-VCP)") (class "Default")
      (node (ref "C53") (pin "2") (pinfunction "2_2") (pintype "passive"))
      (node (ref "IC6") (pin "38") (pinfunction "VCP_38") (pintype "bidirectional"))
    )
    (net (code "133") (name "Net-(IC7-5VOUT)") (class "Default")
      (node (ref "C64") (pin "1") (pinfunction "1_1") (pintype "passive"))
      (node (ref "IC7") (pin "33") (pinfunction "5VOUT_33") (pintype "bidirectional"))
    )
    (net (code "134") (name "Net-(IC7-AIN_IREF)") (class "Default")
      (node (ref "IC7") (pin "30") (pinfunction "AIN_IREF_30") (pintype "bidirectional"))
      (node (ref "R64") (pin "2") (pinfunction "S_2") (pintype "passive"))
    )
    (net (code "135") (name "Net-(IC7-BRA)") (class "Default")
      (node (ref "IC7") (pin "44") (pinfunction "BRA_44") (pintype "bidirectional"))
      (node (ref "R62") (pin "1") (pinfunction "1_1") (pintype "passive"))
    )
    (net (code "136") (name "Net-(IC7-BRB)") (class "Default")
      (node (ref "IC7") (pin "17") (pinfunction "BRB_17") (pintype "bidirectional"))
      (node (ref "R63") (pin "1") (pinfunction "1_1") (pintype "passive"))
    )
    (net (code "137") (name "Net-(IC7-CPI)") (class "Default")
      (node (ref "C67") (pin "1") (pinfunction "1_1") (pintype "passive"))
      (node (ref "IC7") (pin "37") (pinfunction "CPI_37") (pintype "bidirectional"))
    )
    (net (code "138") (name "Net-(IC7-CPO)") (class "Default")
      (node (ref "C67") (pin "2") (pinfunction "2_2") (pintype "passive"))
      (node (ref "IC7") (pin "35") (pinfunction "CPO_35") (pintype "bidirectional"))
    )
    (net (code "139") (name "Net-(IC7-OA1)") (class "Default")
      (node (ref "C71") (pin "1") (pinfunction "1_1") (pintype "passive"))
      (node (ref "IC7") (pin "46") (pinfunction "OA1_46") (pintype "bidirectional"))
      (node (ref "MOT-E2") (pin "1") (pinfunction "S_1") (pintype "passive"))
    )
    (net (code "140") (name "Net-(IC7-OA2)") (class "Default")
      (node (ref "C72") (pin "1") (pinfunction "1_1") (pintype "passive"))
      (node (ref "IC7") (pin "42") (pinfunction "OA2_42") (pintype "bidirectional"))
      (node (ref "MOT-E2") (pin "2") (pinfunction "S_2") (pintype "passive"))
    )
    (net (code "141") (name "Net-(IC7-OB1)") (class "Default")
      (node (ref "C73") (pin "1") (pinfunction "1_1") (pintype "passive"))
      (node (ref "IC7") (pin "15") (pinfunction "OB1_15") (pintype "bidirectional"))
      (node (ref "MOT-E2") (pin "4") (pinfunction "S_4") (pintype "passive"))
    )
    (net (code "142") (name "Net-(IC7-OB2)") (class "Default")
      (node (ref "C74") (pin "1") (pinfunction "1_1") (pintype "passive"))
      (node (ref "IC7") (pin "19") (pinfunction "OB2_19") (pintype "bidirectional"))
      (node (ref "MOT-E2") (pin "3") (pinfunction "S_3") (pintype "passive"))
    )
    (net (code "143") (name "Net-(IC7-VCP)") (class "Default")
      (node (ref "C66") (pin "2") (pinfunction "2_2") (pintype "passive"))
      (node (ref "IC7") (pin "38") (pinfunction "VCP_38") (pintype "bidirectional"))
    )
    (net (code "144") (name "Net-(IC8-5VOUT)") (class "Default")
      (node (ref "C77") (pin "1") (pinfunction "1_1") (pintype "passive"))
      (node (ref "IC8") (pin "33") (pinfunction "5VOUT_33") (pintype "bidirectional"))
    )
    (net (code "145") (name "Net-(IC8-AIN_IREF)") (class "Default")
      (node (ref "IC8") (pin "30") (pinfunction "AIN_IREF_30") (pintype "bidirectional"))
      (node (ref "R68") (pin "2") (pinfunction "S_2") (pintype "passive"))
    )
    (net (code "146") (name "Net-(IC8-BRA)") (class "Default")
      (node (ref "IC8") (pin "44") (pinfunction "BRA_44") (pintype "bidirectional"))
      (node (ref "R66") (pin "1") (pinfunction "1_1") (pintype "passive"))
    )
    (net (code "147") (name "Net-(IC8-BRB)") (class "Default")
      (node (ref "IC8") (pin "17") (pinfunction "BRB_17") (pintype "bidirectional"))
      (node (ref "R67") (pin "1") (pinfunction "1_1") (pintype "passive"))
    )
    (net (code "148") (name "Net-(IC8-CPI)") (class "Default")
      (node (ref "C80") (pin "1") (pinfunction "1_1") (pintype "passive"))
      (node (ref "IC8") (pin "37") (pinfunction "CPI_37") (pintype "bidirectional"))
    )
    (net (code "149") (name "Net-(IC8-CPO)") (class "Default")
      (node (ref "C80") (pin "2") (pinfunction "2_2") (pintype "passive"))
      (node (ref "IC8") (pin "35") (pinfunction "CPO_35") (pintype "bidirectional"))
    )
    (net (code "150") (name "Net-(IC8-OA1)") (class "Default")
      (node (ref "C84") (pin "1") (pinfunction "1_1") (pintype "passive"))
      (node (ref "IC8") (pin "46") (pinfunction "OA1_46") (pintype "bidirectional"))
      (node (ref "MOT-X") (pin "1") (pinfunction "S_1") (pintype "passive"))
    )
    (net (code "151") (name "Net-(IC8-OA2)") (class "Default")
      (node (ref "C85") (pin "1") (pinfunction "1_1") (pintype "passive"))
      (node (ref "IC8") (pin "42") (pinfunction "OA2_42") (pintype "bidirectional"))
      (node (ref "MOT-X") (pin "2") (pinfunction "S_2") (pintype "passive"))
    )
    (net (code "152") (name "Net-(IC8-OB1)") (class "Default")
      (node (ref "C86") (pin "1") (pinfunction "1_1") (pintype "passive"))
      (node (ref "IC8") (pin "15") (pinfunction "OB1_15") (pintype "bidirectional"))
      (node (ref "MOT-X") (pin "4") (pinfunction "S_4") (pintype "passive"))
    )
    (net (code "153") (name "Net-(IC8-OB2)") (class "Default")
      (node (ref "C87") (pin "1") (pinfunction "1_1") (pintype "passive"))
      (node (ref "IC8") (pin "19") (pinfunction "OB2_19") (pintype "bidirectional"))
      (node (ref "MOT-X") (pin "3") (pinfunction "S_3") (pintype "passive"))
    )
    (net (code "154") (name "Net-(IC8-VCP)") (class "Default")
      (node (ref "C79") (pin "2") (pinfunction "2_2") (pintype "passive"))
      (node (ref "IC8") (pin "38") (pinfunction "VCP_38") (pintype "bidirectional"))
    )
    (net (code "155") (name "Net-(IC9-5VOUT)") (class "Default")
      (node (ref "C90") (pin "1") (pinfunction "1_1") (pintype "passive"))
      (node (ref "IC9") (pin "33") (pinfunction "5VOUT_33") (pintype "bidirectional"))
    )
    (net (code "156") (name "Net-(IC9-AIN_IREF)") (class "Default")
      (node (ref "IC9") (pin "30") (pinfunction "AIN_IREF_30") (pintype "bidirectional"))
      (node (ref "R72") (pin "2") (pinfunction "S_2") (pintype "passive"))
    )
    (net (code "157") (name "Net-(IC9-BRA)") (class "Default")
      (node (ref "IC9") (pin "44") (pinfunction "BRA_44") (pintype "bidirectional"))
      (node (ref "R70") (pin "1") (pinfunction "1_1") (pintype "passive"))
    )
    (net (code "158") (name "Net-(IC9-BRB)") (class "Default")
      (node (ref "IC9") (pin "17") (pinfunction "BRB_17") (pintype "bidirectional"))
      (node (ref "R71") (pin "1") (pinfunction "1_1") (pintype "passive"))
    )
    (net (code "159") (name "Net-(IC9-CPI)") (class "Default")
      (node (ref "C93") (pin "1") (pinfunction "1_1") (pintype "passive"))
      (node (ref "IC9") (pin "37") (pinfunction "CPI_37") (pintype "bidirectional"))
    )
    (net (code "160") (name "Net-(IC9-CPO)") (class "Default")
      (node (ref "C93") (pin "2") (pinfunction "2_2") (pintype "passive"))
      (node (ref "IC9") (pin "35") (pinfunction "CPO_35") (pintype "bidirectional"))
    )
    (net (code "161") (name "Net-(IC9-OA1)") (class "Default")
      (node (ref "C97") (pin "1") (pinfunction "1_1") (pintype "passive"))
      (node (ref "IC9") (pin "46") (pinfunction "OA1_46") (pintype "bidirectional"))
      (node (ref "MOT-Y") (pin "1") (pinfunction "S_1") (pintype "passive"))
    )
    (net (code "162") (name "Net-(IC9-OA2)") (class "Default")
      (node (ref "C98") (pin "1") (pinfunction "1_1") (pintype "passive"))
      (node (ref "IC9") (pin "42") (pinfunction "OA2_42") (pintype "bidirectional"))
      (node (ref "MOT-Y") (pin "2") (pinfunction "S_2") (pintype "passive"))
    )
    (net (code "163") (name "Net-(IC9-OB1)") (class "Default")
      (node (ref "C99") (pin "1") (pinfunction "1_1") (pintype "passive"))
      (node (ref "IC9") (pin "15") (pinfunction "OB1_15") (pintype "bidirectional"))
      (node (ref "MOT-Y") (pin "4") (pinfunction "S_4") (pintype "passive"))
    )
    (net (code "164") (name "Net-(IC9-OB2)") (class "Default")
      (node (ref "C100") (pin "1") (pinfunction "1_1") (pintype "passive"))
      (node (ref "IC9") (pin "19") (pinfunction "OB2_19") (pintype "bidirectional"))
      (node (ref "MOT-Y") (pin "3") (pinfunction "S_3") (pintype "passive"))
    )
    (net (code "165") (name "Net-(IC9-VCP)") (class "Default")
      (node (ref "C92") (pin "2") (pinfunction "2_2") (pintype "passive"))
      (node (ref "IC9") (pin "38") (pinfunction "VCP_38") (pintype "bidirectional"))
    )
    (net (code "166") (name "Net-(IC10-5VOUT)") (class "Default")
      (node (ref "C103") (pin "1") (pinfunction "1_1") (pintype "passive"))
      (node (ref "IC10") (pin "33") (pinfunction "5VOUT_33") (pintype "bidirectional"))
    )
    (net (code "167") (name "Net-(IC10-AIN_IREF)") (class "Default")
      (node (ref "IC10") (pin "30") (pinfunction "AIN_IREF_30") (pintype "bidirectional"))
      (node (ref "R76") (pin "2") (pinfunction "S_2") (pintype "passive"))
    )
    (net (code "168") (name "Net-(IC10-BRA)") (class "Default")
      (node (ref "IC10") (pin "44") (pinfunction "BRA_44") (pintype "bidirectional"))
      (node (ref "R74") (pin "1") (pinfunction "1_1") (pintype "passive"))
    )
    (net (code "169") (name "Net-(IC10-BRB)") (class "Default")
      (node (ref "IC10") (pin "17") (pinfunction "BRB_17") (pintype "bidirectional"))
      (node (ref "R75") (pin "1") (pinfunction "1_1") (pintype "passive"))
    )
    (net (code "170") (name "Net-(IC10-CPI)") (class "Default")
      (node (ref "C106") (pin "1") (pinfunction "1_1") (pintype "passive"))
      (node (ref "IC10") (pin "37") (pinfunction "CPI_37") (pintype "bidirectional"))
    )
    (net (code "171") (name "Net-(IC10-CPO)") (class "Default")
      (node (ref "C106") (pin "2") (pinfunction "2_2") (pintype "passive"))
      (node (ref "IC10") (pin "35") (pinfunction "CPO_35") (pintype "bidirectional"))
    )
    (net (code "172") (name "Net-(IC10-OA1)") (class "Default")
      (node (ref "C110") (pin "1") (pinfunction "1_1") (pintype "passive"))
      (node (ref "IC10") (pin "46") (pinfunction "OA1_46") (pintype "bidirectional"))
      (node (ref "MOT-Z2") (pin "1") (pinfunction "S_1") (pintype "passive"))
    )
    (net (code "173") (name "Net-(IC10-OA2)") (class "Default")
      (node (ref "C111") (pin "1") (pinfunction "1_1") (pintype "passive"))
      (node (ref "IC10") (pin "42") (pinfunction "OA2_42") (pintype "bidirectional"))
      (node (ref "MOT-Z1") (pin "2") (pinfunction "S_2") (pintype "passive"))
    )
    (net (code "174") (name "Net-(IC10-OB1)") (class "Default")
      (node (ref "C112") (pin "1") (pinfunction "1_1") (pintype "passive"))
      (node (ref "IC10") (pin "15") (pinfunction "OB1_15") (pintype "bidirectional"))
      (node (ref "MOT-Z2") (pin "4") (pinfunction "S_4") (pintype "passive"))
    )
    (net (code "175") (name "Net-(IC10-OB2)") (class "Default")
      (node (ref "C113") (pin "1") (pinfunction "1_1") (pintype "passive"))
      (node (ref "IC10") (pin "19") (pinfunction "OB2_19") (pintype "bidirectional"))
      (node (ref "MOT-Z1") (pin "3") (pinfunction "S_3") (pintype "passive"))
    )
    (net (code "176") (name "Net-(IC10-VCP)") (class "Default")
      (node (ref "C105") (pin "2") (pinfunction "2_2") (pintype "passive"))
      (node (ref "IC10") (pin "38") (pinfunction "VCP_38") (pintype "bidirectional"))
    )
    (net (code "177") (name "Net-(IC11A-O)") (class "Default")
      (node (ref "IC11") (pin "3") (pinfunction "O_3") (pintype "output"))
      (node (ref "IC11") (pin "4") (pinfunction "I0_4") (pintype "input"))
    )
    (net (code "178") (name "Net-(IC11B-I1)") (class "Default")
      (node (ref "IC11") (pin "5") (pinfunction "I1_5") (pintype "input"))
      (node (ref "IC11") (pin "8") (pinfunction "O_8") (pintype "output"))
    )
    (net (code "179") (name "Net-(IC11C-I1)") (class "Default")
      (node (ref "IC11") (pin "10") (pinfunction "I1_10") (pintype "input"))
      (node (ref "IC11") (pin "11") (pinfunction "O_11") (pintype "output"))
    )
    (net (code "180") (name "Net-(J1-CARD_DETECT)") (class "Default")
      (node (ref "J1") (pin "P9") (pinfunction "CARD_DETECT_P9") (pintype "passive"))
      (node (ref "R27") (pin "2") (pinfunction "2_2") (pintype "passive"))
      (node (ref "R34") (pin "1") (pinfunction "1_1") (pintype "passive"))
    )
    (net (code "181") (name "Net-(J1-CLK)") (class "Default")
      (node (ref "J1") (pin "P5") (pinfunction "CLK_P5") (pintype "input"))
      (node (ref "R30") (pin "2") (pinfunction "2_2") (pintype "passive"))
    )
    (net (code "182") (name "Net-(J1-CMD)") (class "Default")
      (node (ref "J1") (pin "P3") (pinfunction "CMD_P3") (pintype "input"))
      (node (ref "R29") (pin "2") (pinfunction "2_2") (pintype "passive"))
      (node (ref "R35") (pin "1") (pinfunction "1_1") (pintype "passive"))
    )
    (net (code "183") (name "Net-(J1-DAT0)") (class "Default")
      (node (ref "J1") (pin "P7") (pinfunction "DAT0_P7") (pintype "output"))
      (node (ref "R28") (pin "2") (pinfunction "2_2") (pintype "passive"))
    )
    (net (code "184") (name "Net-(J1-DAT1)") (class "Default")
      (node (ref "J1") (pin "P8") (pinfunction "DAT1_P8") (pintype "bidirectional"))
      (node (ref "R32") (pin "2") (pinfunction "2_2") (pintype "passive"))
    )
    (net (code "185") (name "Net-(J1-DAT2)") (class "Default")
      (node (ref "J1") (pin "P1") (pinfunction "DAT2_P1") (pintype "bidirectional"))
      (node (ref "R33") (pin "2") (pinfunction "2_2") (pintype "passive"))
    )
    (net (code "186") (name "Net-(J1-DAT3)") (class "Default")
      (node (ref "J1") (pin "P2") (pinfunction "DAT3_P2") (pintype "input"))
      (node (ref "R31") (pin "2") (pinfunction "2_2") (pintype "passive"))
    )
    (net (code "187") (name "Net-(J2B-1)") (class "Default")
      (node (ref "F2") (pin "2") (pinfunction "2_2") (pintype "passive"))
      (node (ref "J2") (pin "2") (pinfunction "1_2") (pintype "passive"))
      (node (ref "R54") (pin "2") (pinfunction "2_2") (pintype "passive"))
    )
    (net (code "188") (name "Net-(J2C-1)") (class "Default")
      (node (ref "EXT2_L") (pin "C") (pinfunction "C_C") (pintype "passive"))
      (node (ref "J2") (pin "3") (pinfunction "1_3") (pintype "passive"))
      (node (ref "Q4") (pin "5") (pinfunction "D_5") (pintype "passive"))
      (node (ref "Q4") (pin "6") (pinfunction "D_6") (pintype "passive"))
      (node (ref "Q4") (pin "7") (pinfunction "D_7") (pintype "passive"))
      (node (ref "Q4") (pin "8") (pinfunction "D_8") (pintype "passive"))
      (node (ref "Q4") (pin "E1") (pinfunction "D_E1") (pintype "passive"))
      (node (ref "Q4") (pin "E2") (pinfunction "D_E2") (pintype "passive"))
      (node (ref "Q4") (pin "PAD") (pinfunction "D_PAD") (pintype "passive"))
    )
    (net (code "189") (name "Net-(J2D-1)") (class "Default")
      (node (ref "F3") (pin "2") (pinfunction "2_2") (pintype "passive"))
      (node (ref "J2") (pin "4") (pinfunction "1_4") (pintype "passive"))
      (node (ref "R55") (pin "2") (pinfunction "2_2") (pintype "passive"))
    )
    (net (code "190") (name "Net-(L2-2)") (class "Default")
      (node (ref "C10") (pin "1") (pinfunction "1_1") (pintype "passive"))
      (node (ref "C8") (pin "1") (pinfunction "1_1") (pintype "passive"))
      (node (ref "C9") (pin "1") (pinfunction "1_1") (pintype "passive"))
      (node (ref "L2") (pin "P$2") (pinfunction "2_P$2") (pintype "passive"))
      (node (ref "L3") (pin "1") (pinfunction "1_1") (pintype "passive"))
      (node (ref "R6") (pin "2") (pinfunction "2_2") (pintype "passive"))
    )
    (net (code "191") (name "Net-(MOT-Z1A-S)") (class "Default")
      (node (ref "MOT-Z1") (pin "1") (pinfunction "S_1") (pintype "passive"))
      (node (ref "MOT-Z2") (pin "2") (pinfunction "S_2") (pintype "passive"))
    )
    (net (code "192") (name "Net-(MOT-Z1D-S)") (class "Default")
      (node (ref "MOT-Z1") (pin "4") (pinfunction "S_4") (pintype "passive"))
      (node (ref "MOT-Z2") (pin "3") (pinfunction "S_3") (pintype "passive"))
    )
    (net (code "193") (name "Net-(Q1A-G)") (class "Default")
      (node (ref "Q1") (pin "2") (pinfunction "G_2") (pintype "passive"))
      (node (ref "R48") (pin "2") (pinfunction "2_2") (pintype "passive"))
    )
    (net (code "194") (name "Net-(Q1B-G)") (class "Default")
      (node (ref "Q1") (pin "5") (pinfunction "G_5") (pintype "passive"))
      (node (ref "R49") (pin "2") (pinfunction "2_2") (pintype "passive"))
    )
    (net (code "195") (name "Net-(Q2A-G)") (class "Default")
      (node (ref "Q2") (pin "2") (pinfunction "G_2") (pintype "passive"))
      (node (ref "R50") (pin "2") (pinfunction "2_2") (pintype "passive"))
    )
    (net (code "196") (name "Net-(Q2B-G)") (class "Default")
      (node (ref "Q2") (pin "5") (pinfunction "G_5") (pintype "passive"))
      (node (ref "R51") (pin "2") (pinfunction "2_2") (pintype "passive"))
    )
    (net (code "197") (name "Net-(Q3-G)") (class "Default")
      (node (ref "Q3") (pin "4") (pinfunction "G_4") (pintype "passive"))
      (node (ref "R52") (pin "2") (pinfunction "2_2") (pintype "passive"))
    )
    (net (code "198") (name "Net-(Q4-G)") (class "Default")
      (node (ref "Q4") (pin "4") (pinfunction "G_4") (pintype "passive"))
      (node (ref "R53") (pin "2") (pinfunction "2_2") (pintype "passive"))
    )
    (net (code "199") (name "Net-(R8-Pad1)") (class "Default")
      (node (ref "R8") (pin "1") (pinfunction "1_1") (pintype "passive"))
      (node (ref "VIN") (pin "C") (pinfunction "C_C") (pintype "passive"))
    )
    (net (code "200") (name "Net-(R11-Pad1)") (class "Default")
      (node (ref "R11") (pin "1") (pinfunction "1_1") (pintype "passive"))
      (node (ref "USB_L") (pin "C") (pinfunction "C_C") (pintype "passive"))
    )
    (net (code "201") (name "Net-(R60-E)") (class "Default")
      (node (ref "R60") (pin "3") (pinfunction "E_3") (pintype "passive"))
      (node (ref "R61") (pin "1") (pinfunction "1_1") (pintype "passive"))
    )
    (net (code "202") (name "Net-(R64-E)") (class "Default")
      (node (ref "R64") (pin "3") (pinfunction "E_3") (pintype "passive"))
      (node (ref "R65") (pin "1") (pinfunction "1_1") (pintype "passive"))
    )
    (net (code "203") (name "Net-(R68-E)") (class "Default")
      (node (ref "R68") (pin "3") (pinfunction "E_3") (pintype "passive"))
      (node (ref "R69") (pin "1") (pinfunction "1_1") (pintype "passive"))
    )
    (net (code "204") (name "Net-(R72-E)") (class "Default")
      (node (ref "R72") (pin "3") (pinfunction "E_3") (pintype "passive"))
      (node (ref "R73") (pin "1") (pinfunction "1_1") (pintype "passive"))
    )
    (net (code "205") (name "Net-(R76-E)") (class "Default")
      (node (ref "R76") (pin "3") (pinfunction "E_3") (pintype "passive"))
      (node (ref "R77") (pin "1") (pinfunction "1_1") (pintype "passive"))
    )
    (net (code "206") (name "Net-(X_STOPA-S)") (class "Default")
      (node (ref "R36") (pin "2") (pinfunction "2_2") (pintype "passive"))
      (node (ref "R39") (pin "1") (pinfunction "1_1") (pintype "passive"))
      (node (ref "X_STOP") (pin "1") (pinfunction "S_1") (pintype "passive"))
    )
    (net (code "207") (name "Net-(Y_STOPA-S)") (class "Default")
      (node (ref "R37") (pin "2") (pinfunction "2_2") (pintype "passive"))
      (node (ref "R40") (pin "1") (pinfunction "1_1") (pintype "passive"))
      (node (ref "Y_STOP") (pin "1") (pinfunction "S_1") (pintype "passive"))
    )
    (net (code "208") (name "Net-(Z_STOPA-S)") (class "Default")
      (node (ref "R38") (pin "2") (pinfunction "2_2") (pintype "passive"))
      (node (ref "R41") (pin "1") (pinfunction "1_1") (pintype "passive"))
      (node (ref "Z_STOP") (pin "1") (pinfunction "S_1") (pintype "passive"))
    )
    (net (code "209") (name "unconnected-(ESP8266-ADC-Pad2)") (class "Default")
      (node (ref "ESP8266") (pin "2") (pinfunction "ADC_2") (pintype "passive"))
    )
    (net (code "210") (name "unconnected-(ESP8266-GPIO2-Pad11)") (class "Default")
      (node (ref "ESP8266") (pin "11") (pinfunction "GPIO2_11") (pintype "bidirectional"))
    )
    (net (code "211") (name "unconnected-(ESP8266-GPIO5-Pad13)") (class "Default")
      (node (ref "ESP8266") (pin "13") (pinfunction "GPIO5_13") (pintype "bidirectional"))
    )
    (net (code "212") (name "unconnected-(ESP8266-GPIO16-Pad4)") (class "Default")
      (node (ref "ESP8266") (pin "4") (pinfunction "GPIO16_4") (pintype "bidirectional"))
    )
    (net (code "213") (name "unconnected-(EXP1B-S-Pad10)") (class "Default")
      (node (ref "EXP1") (pin "10") (pinfunction "S_10") (pintype "passive"))
    )
    (net (code "214") (name "unconnected-(EXP1H-S-Pad7)") (class "Default")
      (node (ref "EXP1") (pin "7") (pinfunction "S_7") (pintype "passive"))
    )
    (net (code "215") (name "unconnected-(EXP1I-S-Pad8)") (class "Default")
      (node (ref "EXP1") (pin "8") (pinfunction "S_8") (pintype "passive"))
    )
    (net (code "216") (name "unconnected-(EXP2G-S-Pad6)") (class "Default")
      (node (ref "EXP2") (pin "6") (pinfunction "S_6") (pintype "passive"))
    )
    (net (code "217") (name "unconnected-(EXP2H-S-Pad7)") (class "Default")
      (node (ref "EXP2") (pin "7") (pinfunction "S_7") (pintype "passive"))
    )
    (net (code "218") (name "unconnected-(EXP2I-S-Pad8)") (class "Default")
      (node (ref "EXP2") (pin "8") (pinfunction "S_8") (pintype "passive"))
    )
    (net (code "219") (name "unconnected-(IC3-PB2{slash}AD6-Pad7)") (class "Default")
      (node (ref "IC3") (pin "7") (pinfunction "PB2/AD6_7") (pintype "bidirectional"))
    )
    (net (code "220") (name "unconnected-(IC3-PB3{slash}AD7-Pad9)") (class "Default")
      (node (ref "IC3") (pin "9") (pinfunction "PB3/AD7_9") (pintype "bidirectional"))
    )
    (net (code "221") (name "unconnected-(IC3-PB13{slash}DAC0-Pad93)") (class "Default")
      (node (ref "IC3") (pin "93") (pinfunction "PB13/DAC0_93") (pintype "bidirectional"))
    )
    (net (code "222") (name "unconnected-(IC3-PC18-Pad78)") (class "Default")
      (node (ref "IC3") (pin "78") (pinfunction "PC18_78") (pintype "bidirectional"))
    )
    (net (code "223") (name "unconnected-(IC3-PC23-Pad90)") (class "Default")
      (node (ref "IC3") (pin "90") (pinfunction "PC23_90") (pintype "bidirectional"))
    )
    (net (code "224") (name "unconnected-(IC3-PC24-Pad92)") (class "Default")
      (node (ref "IC3") (pin "92") (pinfunction "PC24_92") (pintype "bidirectional"))
    )
    (net (code "225") (name "unconnected-(IC3-PC25-Pad94)") (class "Default")
      (node (ref "IC3") (pin "94") (pinfunction "PC25_94") (pintype "bidirectional"))
    )
    (net (code "226") (name "unconnected-(IC3-PC26-Pad13)") (class "Default")
      (node (ref "IC3") (pin "13") (pinfunction "PC26_13") (pintype "bidirectional"))
    )
    (net (code "227") (name "unconnected-(IC3-PC27-Pad17)") (class "Default")
      (node (ref "IC3") (pin "17") (pinfunction "PC27_17") (pintype "bidirectional"))
    )
    (net (code "228") (name "unconnected-(IC3-PC31-Pad8)") (class "Default")
      (node (ref "IC3") (pin "8") (pinfunction "PC31_8") (pintype "bidirectional"))
    )
    (net (code "229") (name "unconnected-(IC3-TMS{slash}SWDIO{slash}PB6-Pad79)") (class "Default")
      (node (ref "IC3") (pin "79") (pinfunction "TMS/SWDIO/PB6_79") (pintype "bidirectional"))
    )
    (net (code "230") (name "unconnected-(IC4A-O-Pad3)") (class "Default")
      (node (ref "IC4") (pin "3") (pinfunction "O_3") (pintype "tri_state"))
    )
    (net (code "231") (name "unconnected-(IC5A-O-Pad3)") (class "Default")
      (node (ref "IC5") (pin "3") (pinfunction "O_3") (pintype "output"))
    )
    (net (code "232") (name "unconnected-(IC6-ENCA_DCIN_CFG5-Pad25)") (class "Default")
      (node (ref "IC6") (pin "25") (pinfunction "ENCA_DCIN_CFG5_25") (pintype "bidirectional"))
    )
    (net (code "233") (name "unconnected-(IC6-ENCN_DCO-Pad23)") (class "Default")
      (node (ref "IC6") (pin "23") (pinfunction "ENCN_DCO_23") (pintype "bidirectional"))
    )
    (net (code "234") (name "unconnected-(IC6-SD_MODE-Pad11)") (class "Default")
      (node (ref "IC6") (pin "11") (pinfunction "SD_MODE_11") (pintype "bidirectional"))
    )
    (net (code "235") (name "unconnected-(IC6-SPI_MODE-Pad12)") (class "Default")
      (node (ref "IC6") (pin "12") (pinfunction "SPI_MODE_12") (pintype "bidirectional"))
    )
    (net (code "236") (name "unconnected-(IC6-SWN_DIAG0-Pad26)") (class "Default")
      (node (ref "IC6") (pin "26") (pinfunction "SWN_DIAG0_26") (pintype "bidirectional"))
    )
    (net (code "237") (name "unconnected-(IC6-SWSEL-Pad28)") (class "Default")
      (node (ref "IC6") (pin "28") (pinfunction "SWSEL_28") (pintype "bidirectional"))
    )
    (net (code "238") (name "unconnected-(IC7-ENCA_DCIN_CFG5-Pad25)") (class "Default")
      (node (ref "IC7") (pin "25") (pinfunction "ENCA_DCIN_CFG5_25") (pintype "bidirectional"))
    )
    (net (code "239") (name "unconnected-(IC7-ENCN_DCO-Pad23)") (class "Default")
      (node (ref "IC7") (pin "23") (pinfunction "ENCN_DCO_23") (pintype "bidirectional"))
    )
    (net (code "240") (name "unconnected-(IC7-SD_MODE-Pad11)") (class "Default")
      (node (ref "IC7") (pin "11") (pinfunction "SD_MODE_11") (pintype "bidirectional"))
    )
    (net (code "241") (name "unconnected-(IC7-SPI_MODE-Pad12)") (class "Default")
      (node (ref "IC7") (pin "12") (pinfunction "SPI_MODE_12") (pintype "bidirectional"))
    )
    (net (code "242") (name "unconnected-(IC7-SWN_DIAG0-Pad26)") (class "Default")
      (node (ref "IC7") (pin "26") (pinfunction "SWN_DIAG0_26") (pintype "bidirectional"))
    )
    (net (code "243") (name "unconnected-(IC7-SWSEL-Pad28)") (class "Default")
      (node (ref "IC7") (pin "28") (pinfunction "SWSEL_28") (pintype "bidirectional"))
    )
    (net (code "244") (name "unconnected-(IC8-ENCA_DCIN_CFG5-Pad25)") (class "Default")
      (node (ref "IC8") (pin "25") (pinfunction "ENCA_DCIN_CFG5_25") (pintype "bidirectional"))
    )
    (net (code "245") (name "unconnected-(IC8-ENCN_DCO-Pad23)") (class "Default")
      (node (ref "IC8") (pin "23") (pinfunction "ENCN_DCO_23") (pintype "bidirectional"))
    )
    (net (code "246") (name "unconnected-(IC8-SD_MODE-Pad11)") (class "Default")
      (node (ref "IC8") (pin "11") (pinfunction "SD_MODE_11") (pintype "bidirectional"))
    )
    (net (code "247") (name "unconnected-(IC8-SPI_MODE-Pad12)") (class "Default")
      (node (ref "IC8") (pin "12") (pinfunction "SPI_MODE_12") (pintype "bidirectional"))
    )
    (net (code "248") (name "unconnected-(IC8-SWN_DIAG0-Pad26)") (class "Default")
      (node (ref "IC8") (pin "26") (pinfunction "SWN_DIAG0_26") (pintype "bidirectional"))
    )
    (net (code "249") (name "unconnected-(IC8-SWSEL-Pad28)") (class "Default")
      (node (ref "IC8") (pin "28") (pinfunction "SWSEL_28") (pintype "bidirectional"))
    )
    (net (code "250") (name "unconnected-(IC9-ENCA_DCIN_CFG5-Pad25)") (class "Default")
      (node (ref "IC9") (pin "25") (pinfunction "ENCA_DCIN_CFG5_25") (pintype "bidirectional"))
    )
    (net (code "251") (name "unconnected-(IC9-ENCN_DCO-Pad23)") (class "Default")
      (node (ref "IC9") (pin "23") (pinfunction "ENCN_DCO_23") (pintype "bidirectional"))
    )
    (net (code "252") (name "unconnected-(IC9-SD_MODE-Pad11)") (class "Default")
      (node (ref "IC9") (pin "11") (pinfunction "SD_MODE_11") (pintype "bidirectional"))
    )
    (net (code "253") (name "unconnected-(IC9-SPI_MODE-Pad12)") (class "Default")
      (node (ref "IC9") (pin "12") (pinfunction "SPI_MODE_12") (pintype "bidirectional"))
    )
    (net (code "254") (name "unconnected-(IC9-SWN_DIAG0-Pad26)") (class "Default")
      (node (ref "IC9") (pin "26") (pinfunction "SWN_DIAG0_26") (pintype "bidirectional"))
    )
    (net (code "255") (name "unconnected-(IC9-SWSEL-Pad28)") (class "Default")
      (node (ref "IC9") (pin "28") (pinfunction "SWSEL_28") (pintype "bidirectional"))
    )
    (net (code "256") (name "unconnected-(IC10-ENCA_DCIN_CFG5-Pad25)") (class "Default")
      (node (ref "IC10") (pin "25") (pinfunction "ENCA_DCIN_CFG5_25") (pintype "bidirectional"))
    )
    (net (code "257") (name "unconnected-(IC10-ENCN_DCO-Pad23)") (class "Default")
      (node (ref "IC10") (pin "23") (pinfunction "ENCN_DCO_23") (pintype "bidirectional"))
    )
    (net (code "258") (name "unconnected-(IC10-SD_MODE-Pad11)") (class "Default")
      (node (ref "IC10") (pin "11") (pinfunction "SD_MODE_11") (pintype "bidirectional"))
    )
    (net (code "259") (name "unconnected-(IC10-SPI_MODE-Pad12)") (class "Default")
      (node (ref "IC10") (pin "12") (pinfunction "SPI_MODE_12") (pintype "bidirectional"))
    )
    (net (code "260") (name "unconnected-(IC10-SWN_DIAG0-Pad26)") (class "Default")
      (node (ref "IC10") (pin "26") (pinfunction "SWN_DIAG0_26") (pintype "bidirectional"))
    )
    (net (code "261") (name "unconnected-(IC10-SWSEL-Pad28)") (class "Default")
      (node (ref "IC10") (pin "28") (pinfunction "SWSEL_28") (pintype "bidirectional"))
    )
    (net (code "262") (name "unconnected-(RESET-P-PadA)") (class "Default")
      (node (ref "RESET") (pin "A") (pinfunction "P_A") (pintype "passive"))
    )
  )
)
